# USB.net
KiCad netlist of a schematic drawn in Altium Designer
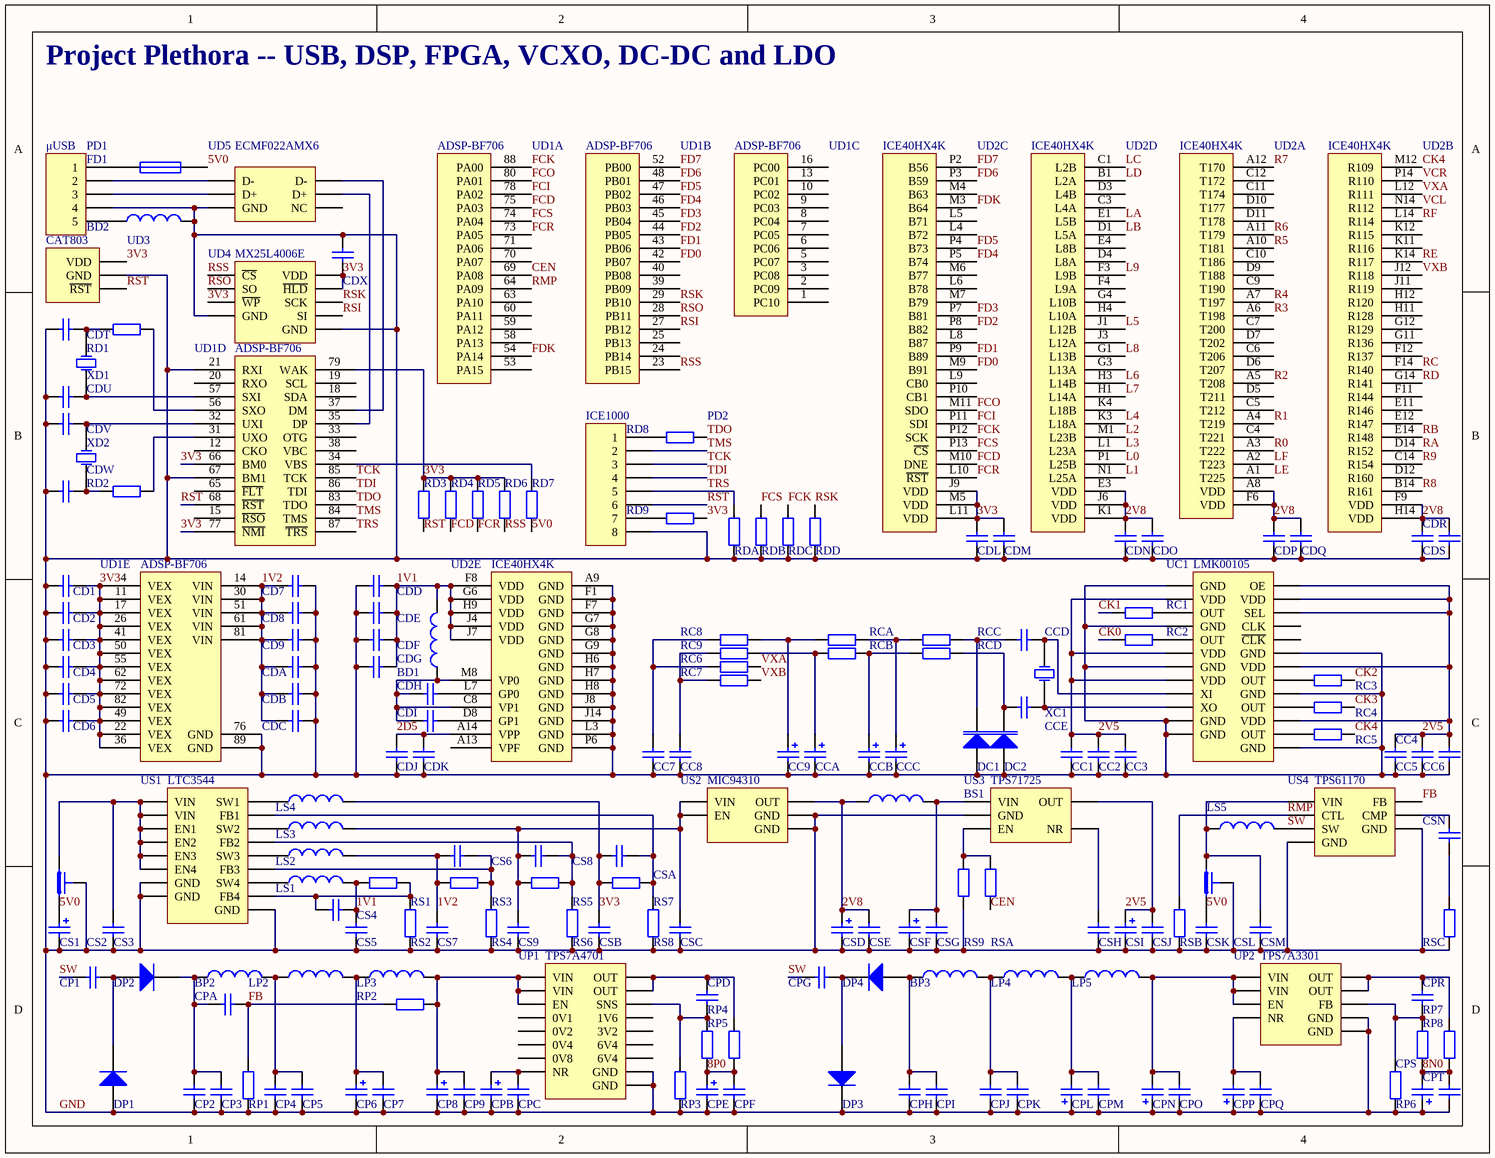
[diagram p0: USB.SchDoc]

(export (version "E")
  (design (tool "Eeschema 10.0.6"))
  (components
    (comp (ref "BD1")
      (value "Inductor")
      (footprint "0402")
      (fields (field (name "PUBLISHER") "Altium Limited"))
      (libsource (lib "Miscellaneous Devices") (part "Inductor"))
    )
    (comp (ref "BD2")
      (value "Inductor")
      (footprint "0402")
      (fields (field (name "PUBLISHER") "Altium Limited"))
      (libsource (lib "Miscellaneous Devices") (part "Inductor"))
    )
    (comp (ref "BP2")
      (value "Inductor")
      (footprint "0402")
      (fields (field (name "PUBLISHER") "Altium Limited"))
      (libsource (lib "Miscellaneous Devices") (part "Inductor"))
    )
    (comp (ref "BP3")
      (value "Inductor")
      (footprint "0402")
      (fields (field (name "PUBLISHER") "Altium Limited"))
      (libsource (lib "Miscellaneous Devices") (part "Inductor"))
    )
    (comp (ref "BS1")
      (value "Inductor")
      (footprint "0402")
      (fields (field (name "PUBLISHER") "Altium Limited"))
      (libsource (lib "Miscellaneous Devices") (part "Inductor"))
    )
    (comp (ref "CC1")
      (value "Cap")
      (footprint "0603")
      (description "Capacitor")
      (fields (field (name "PUBLISHER") "Altium Limited"))
      (libsource (lib "Miscellaneous Devices") (part "Cap"))
    )
    (comp (ref "CC2")
      (value "Cap")
      (footprint "0402")
      (description "Capacitor")
      (fields (field (name "PUBLISHER") "Altium Limited"))
      (libsource (lib "Miscellaneous Devices") (part "Cap"))
    )
    (comp (ref "CC3")
      (value "Cap")
      (footprint "0402")
      (description "Capacitor")
      (fields (field (name "PUBLISHER") "Altium Limited"))
      (libsource (lib "Miscellaneous Devices") (part "Cap"))
    )
    (comp (ref "CC4")
      (value "Cap")
      (footprint "0402")
      (description "Capacitor")
      (fields (field (name "PUBLISHER") "Altium Limited"))
      (libsource (lib "Miscellaneous Devices") (part "Cap"))
    )
    (comp (ref "CC5")
      (value "Cap")
      (footprint "0402")
      (description "Capacitor")
      (fields (field (name "PUBLISHER") "Altium Limited"))
      (libsource (lib "Miscellaneous Devices") (part "Cap"))
    )
    (comp (ref "CC6")
      (value "Cap")
      (footprint "0402")
      (description "Capacitor")
      (fields (field (name "PUBLISHER") "Altium Limited"))
      (libsource (lib "Miscellaneous Devices") (part "Cap"))
    )
    (comp (ref "CC7")
      (value "Cap")
      (footprint "0402")
      (description "Capacitor")
      (fields (field (name "PUBLISHER") "Altium Limited"))
      (libsource (lib "Miscellaneous Devices") (part "Cap"))
    )
    (comp (ref "CC8")
      (value "Cap")
      (footprint "0402")
      (description "Capacitor")
      (fields (field (name "PUBLISHER") "Altium Limited"))
      (libsource (lib "Miscellaneous Devices") (part "Cap"))
    )
    (comp (ref "CC9")
      (value "Cap Pol2")
      (footprint "0603")
      (description "Polarized Capacitor (Axial)")
      (fields (field (name "PUBLISHER") "Altium Limited"))
      (libsource (lib "Miscellaneous Devices") (part "Cap Pol2"))
    )
    (comp (ref "CCA")
      (value "Cap Pol2")
      (footprint "0603")
      (description "Polarized Capacitor (Axial)")
      (fields (field (name "PUBLISHER") "Altium Limited"))
      (libsource (lib "Miscellaneous Devices") (part "Cap Pol2"))
    )
    (comp (ref "CCB")
      (value "Cap Pol2")
      (footprint "0603")
      (description "Polarized Capacitor (Axial)")
      (fields (field (name "PUBLISHER") "Altium Limited"))
      (libsource (lib "Miscellaneous Devices") (part "Cap Pol2"))
    )
    (comp (ref "CCC")
      (value "Cap Pol2")
      (footprint "0603")
      (description "Polarized Capacitor (Axial)")
      (fields (field (name "PUBLISHER") "Altium Limited"))
      (libsource (lib "Miscellaneous Devices") (part "Cap Pol2"))
    )
    (comp (ref "CCD")
      (value "Cap")
      (footprint "0402")
      (description "Capacitor")
      (fields (field (name "PUBLISHER") "Altium Limited"))
      (libsource (lib "Miscellaneous Devices") (part "Cap"))
    )
    (comp (ref "CCE")
      (value "Cap")
      (footprint "0402")
      (description "Capacitor")
      (fields (field (name "PUBLISHER") "Altium Limited"))
      (libsource (lib "Miscellaneous Devices") (part "Cap"))
    )
    (comp (ref "CD1")
      (value "Cap")
      (footprint "0402")
      (description "Capacitor")
      (fields (field (name "PUBLISHER") "Altium Limited"))
      (libsource (lib "Miscellaneous Devices") (part "Cap"))
    )
    (comp (ref "CD2")
      (value "Cap")
      (footprint "0402")
      (description "Capacitor")
      (fields (field (name "PUBLISHER") "Altium Limited"))
      (libsource (lib "Miscellaneous Devices") (part "Cap"))
    )
    (comp (ref "CD3")
      (value "Cap")
      (footprint "0402")
      (description "Capacitor")
      (fields (field (name "PUBLISHER") "Altium Limited"))
      (libsource (lib "Miscellaneous Devices") (part "Cap"))
    )
    (comp (ref "CD4")
      (value "Cap")
      (footprint "0402")
      (description "Capacitor")
      (fields (field (name "PUBLISHER") "Altium Limited"))
      (libsource (lib "Miscellaneous Devices") (part "Cap"))
    )
    (comp (ref "CD5")
      (value "Cap")
      (footprint "0402")
      (description "Capacitor")
      (fields (field (name "PUBLISHER") "Altium Limited"))
      (libsource (lib "Miscellaneous Devices") (part "Cap"))
    )
    (comp (ref "CD6")
      (value "Cap")
      (footprint "0402")
      (description "Capacitor")
      (fields (field (name "PUBLISHER") "Altium Limited"))
      (libsource (lib "Miscellaneous Devices") (part "Cap"))
    )
    (comp (ref "CD7")
      (value "Cap")
      (footprint "0402")
      (description "Capacitor")
      (fields (field (name "PUBLISHER") "Altium Limited"))
      (libsource (lib "Miscellaneous Devices") (part "Cap"))
    )
    (comp (ref "CD8")
      (value "Cap")
      (footprint "0402")
      (description "Capacitor")
      (fields (field (name "PUBLISHER") "Altium Limited"))
      (libsource (lib "Miscellaneous Devices") (part "Cap"))
    )
    (comp (ref "CD9")
      (value "Cap")
      (footprint "0402")
      (description "Capacitor")
      (fields (field (name "PUBLISHER") "Altium Limited"))
      (libsource (lib "Miscellaneous Devices") (part "Cap"))
    )
    (comp (ref "CDA")
      (value "Cap")
      (footprint "0402")
      (description "Capacitor")
      (fields (field (name "PUBLISHER") "Altium Limited"))
      (libsource (lib "Miscellaneous Devices") (part "Cap"))
    )
    (comp (ref "CDB")
      (value "Cap")
      (footprint "0402")
      (description "Capacitor")
      (fields (field (name "PUBLISHER") "Altium Limited"))
      (libsource (lib "Miscellaneous Devices") (part "Cap"))
    )
    (comp (ref "CDC")
      (value "Cap")
      (footprint "0402")
      (description "Capacitor")
      (fields (field (name "PUBLISHER") "Altium Limited"))
      (libsource (lib "Miscellaneous Devices") (part "Cap"))
    )
    (comp (ref "CDD")
      (value "Cap")
      (footprint "0402")
      (description "Capacitor")
      (fields (field (name "PUBLISHER") "Altium Limited"))
      (libsource (lib "Miscellaneous Devices") (part "Cap"))
    )
    (comp (ref "CDE")
      (value "Cap")
      (footprint "0402")
      (description "Capacitor")
      (fields (field (name "PUBLISHER") "Altium Limited"))
      (libsource (lib "Miscellaneous Devices") (part "Cap"))
    )
    (comp (ref "CDF")
      (value "Cap")
      (footprint "0402")
      (description "Capacitor")
      (fields (field (name "PUBLISHER") "Altium Limited"))
      (libsource (lib "Miscellaneous Devices") (part "Cap"))
    )
    (comp (ref "CDG")
      (value "Cap")
      (footprint "0402")
      (description "Capacitor")
      (fields (field (name "PUBLISHER") "Altium Limited"))
      (libsource (lib "Miscellaneous Devices") (part "Cap"))
    )
    (comp (ref "CDH")
      (value "Cap")
      (footprint "0402")
      (description "Capacitor")
      (fields (field (name "PUBLISHER") "Altium Limited"))
      (libsource (lib "Miscellaneous Devices") (part "Cap"))
    )
    (comp (ref "CDI")
      (value "Cap")
      (footprint "0402")
      (description "Capacitor")
      (fields (field (name "PUBLISHER") "Altium Limited"))
      (libsource (lib "Miscellaneous Devices") (part "Cap"))
    )
    (comp (ref "CDJ")
      (value "Cap")
      (footprint "0402")
      (description "Capacitor")
      (fields (field (name "PUBLISHER") "Altium Limited"))
      (libsource (lib "Miscellaneous Devices") (part "Cap"))
    )
    (comp (ref "CDK")
      (value "Cap")
      (footprint "0402")
      (description "Capacitor")
      (fields (field (name "PUBLISHER") "Altium Limited"))
      (libsource (lib "Miscellaneous Devices") (part "Cap"))
    )
    (comp (ref "CDL")
      (value "Cap")
      (footprint "0402")
      (description "Capacitor")
      (fields (field (name "PUBLISHER") "Altium Limited"))
      (libsource (lib "Miscellaneous Devices") (part "Cap"))
    )
    (comp (ref "CDM")
      (value "Cap")
      (footprint "0402")
      (description "Capacitor")
      (fields (field (name "PUBLISHER") "Altium Limited"))
      (libsource (lib "Miscellaneous Devices") (part "Cap"))
    )
    (comp (ref "CDN")
      (value "Cap")
      (footprint "0402")
      (description "Capacitor")
      (fields (field (name "PUBLISHER") "Altium Limited"))
      (libsource (lib "Miscellaneous Devices") (part "Cap"))
    )
    (comp (ref "CDO")
      (value "Cap")
      (footprint "0402")
      (description "Capacitor")
      (fields (field (name "PUBLISHER") "Altium Limited"))
      (libsource (lib "Miscellaneous Devices") (part "Cap"))
    )
    (comp (ref "CDP")
      (value "Cap")
      (footprint "0402")
      (description "Capacitor")
      (fields (field (name "PUBLISHER") "Altium Limited"))
      (libsource (lib "Miscellaneous Devices") (part "Cap"))
    )
    (comp (ref "CDQ")
      (value "Cap")
      (footprint "0402")
      (description "Capacitor")
      (fields (field (name "PUBLISHER") "Altium Limited"))
      (libsource (lib "Miscellaneous Devices") (part "Cap"))
    )
    (comp (ref "CDR")
      (value "Cap")
      (footprint "0402")
      (description "Capacitor")
      (fields (field (name "PUBLISHER") "Altium Limited"))
      (libsource (lib "Miscellaneous Devices") (part "Cap"))
    )
    (comp (ref "CDS")
      (value "Cap")
      (footprint "0402")
      (description "Capacitor")
      (fields (field (name "PUBLISHER") "Altium Limited"))
      (libsource (lib "Miscellaneous Devices") (part "Cap"))
    )
    (comp (ref "CDT")
      (value "Cap")
      (footprint "0402")
      (description "Capacitor")
      (fields (field (name "PUBLISHER") "Altium Limited"))
      (libsource (lib "Miscellaneous Devices") (part "Cap"))
    )
    (comp (ref "CDU")
      (value "Cap")
      (footprint "0402")
      (description "Capacitor")
      (fields (field (name "PUBLISHER") "Altium Limited"))
      (libsource (lib "Miscellaneous Devices") (part "Cap"))
    )
    (comp (ref "CDV")
      (value "Cap")
      (footprint "0402")
      (description "Capacitor")
      (fields (field (name "PUBLISHER") "Altium Limited"))
      (libsource (lib "Miscellaneous Devices") (part "Cap"))
    )
    (comp (ref "CDW")
      (value "Cap")
      (footprint "0402")
      (description "Capacitor")
      (fields (field (name "PUBLISHER") "Altium Limited"))
      (libsource (lib "Miscellaneous Devices") (part "Cap"))
    )
    (comp (ref "CDX")
      (value "Cap")
      (footprint "0402")
      (description "Capacitor")
      (fields (field (name "PUBLISHER") "Altium Limited"))
      (libsource (lib "Miscellaneous Devices") (part "Cap"))
    )
    (comp (ref "CP1")
      (value "Cap")
      (footprint "0402")
      (description "Capacitor")
      (fields (field (name "PUBLISHER") "Altium Limited"))
      (libsource (lib "Miscellaneous Devices") (part "Cap"))
    )
    (comp (ref "CP2")
      (value "Cap")
      (footprint "0805")
      (description "Capacitor")
      (fields (field (name "PUBLISHER") "Altium Limited"))
      (libsource (lib "Miscellaneous Devices") (part "Cap"))
    )
    (comp (ref "CP3")
      (value "Cap")
      (footprint "0805")
      (description "Capacitor")
      (fields (field (name "PUBLISHER") "Altium Limited"))
      (libsource (lib "Miscellaneous Devices") (part "Cap"))
    )
    (comp (ref "CP4")
      (value "Cap")
      (footprint "0805")
      (description "Capacitor")
      (fields (field (name "PUBLISHER") "Altium Limited"))
      (libsource (lib "Miscellaneous Devices") (part "Cap"))
    )
    (comp (ref "CP5")
      (value "Cap")
      (footprint "0805")
      (description "Capacitor")
      (fields (field (name "PUBLISHER") "Altium Limited"))
      (libsource (lib "Miscellaneous Devices") (part "Cap"))
    )
    (comp (ref "CP6")
      (value "Cap Pol2")
      (footprint "6032")
      (description "Polarized Capacitor (Axial)")
      (fields (field (name "PUBLISHER") "Altium Limited"))
      (libsource (lib "Miscellaneous Devices") (part "Cap Pol2"))
    )
    (comp (ref "CP7")
      (value "Cap")
      (footprint "0805")
      (description "Capacitor")
      (fields (field (name "PUBLISHER") "Altium Limited"))
      (libsource (lib "Miscellaneous Devices") (part "Cap"))
    )
    (comp (ref "CP8")
      (value "Cap Pol2")
      (footprint "6032")
      (description "Polarized Capacitor (Axial)")
      (fields (field (name "PUBLISHER") "Altium Limited"))
      (libsource (lib "Miscellaneous Devices") (part "Cap Pol2"))
    )
    (comp (ref "CP9")
      (value "Cap")
      (footprint "0805")
      (description "Capacitor")
      (fields (field (name "PUBLISHER") "Altium Limited"))
      (libsource (lib "Miscellaneous Devices") (part "Cap"))
    )
    (comp (ref "CPA")
      (value "Cap")
      (footprint "0402")
      (description "Capacitor")
      (fields (field (name "PUBLISHER") "Altium Limited"))
      (libsource (lib "Miscellaneous Devices") (part "Cap"))
    )
    (comp (ref "CPB")
      (value "Cap Pol2")
      (footprint "0603")
      (description "Polarized Capacitor (Axial)")
      (fields (field (name "PUBLISHER") "Altium Limited"))
      (libsource (lib "Miscellaneous Devices") (part "Cap Pol2"))
    )
    (comp (ref "CPC")
      (value "Cap")
      (footprint "0603")
      (description "Capacitor")
      (fields (field (name "PUBLISHER") "Altium Limited"))
      (libsource (lib "Miscellaneous Devices") (part "Cap"))
    )
    (comp (ref "CPD")
      (value "Cap")
      (footprint "0402")
      (description "Capacitor")
      (fields (field (name "PUBLISHER") "Altium Limited"))
      (libsource (lib "Miscellaneous Devices") (part "Cap"))
    )
    (comp (ref "CPE")
      (value "Cap Pol2")
      (footprint "6032")
      (description "Polarized Capacitor (Axial)")
      (fields (field (name "PUBLISHER") "Altium Limited"))
      (libsource (lib "Miscellaneous Devices") (part "Cap Pol2"))
    )
    (comp (ref "CPF")
      (value "Cap")
      (footprint "0805")
      (description "Capacitor")
      (fields (field (name "PUBLISHER") "Altium Limited"))
      (libsource (lib "Miscellaneous Devices") (part "Cap"))
    )
    (comp (ref "CPG")
      (value "Cap")
      (footprint "0402")
      (description "Capacitor")
      (fields (field (name "PUBLISHER") "Altium Limited"))
      (libsource (lib "Miscellaneous Devices") (part "Cap"))
    )
    (comp (ref "CPH")
      (value "Cap")
      (footprint "0805")
      (description "Capacitor")
      (fields (field (name "PUBLISHER") "Altium Limited"))
      (libsource (lib "Miscellaneous Devices") (part "Cap"))
    )
    (comp (ref "CPI")
      (value "Cap")
      (footprint "0805")
      (description "Capacitor")
      (fields (field (name "PUBLISHER") "Altium Limited"))
      (libsource (lib "Miscellaneous Devices") (part "Cap"))
    )
    (comp (ref "CPJ")
      (value "Cap")
      (footprint "0805")
      (description "Capacitor")
      (fields (field (name "PUBLISHER") "Altium Limited"))
      (libsource (lib "Miscellaneous Devices") (part "Cap"))
    )
    (comp (ref "CPK")
      (value "Cap")
      (footprint "0805")
      (description "Capacitor")
      (fields (field (name "PUBLISHER") "Altium Limited"))
      (libsource (lib "Miscellaneous Devices") (part "Cap"))
    )
    (comp (ref "CPL")
      (value "Cap Pol2")
      (footprint "6032")
      (description "Polarized Capacitor (Axial)")
      (fields (field (name "PUBLISHER") "Altium Limited"))
      (libsource (lib "Miscellaneous Devices") (part "Cap Pol2"))
    )
    (comp (ref "CPM")
      (value "Cap")
      (footprint "0805")
      (description "Capacitor")
      (fields (field (name "PUBLISHER") "Altium Limited"))
      (libsource (lib "Miscellaneous Devices") (part "Cap"))
    )
    (comp (ref "CPN")
      (value "Cap Pol2")
      (footprint "6032")
      (description "Polarized Capacitor (Axial)")
      (fields (field (name "PUBLISHER") "Altium Limited"))
      (libsource (lib "Miscellaneous Devices") (part "Cap Pol2"))
    )
    (comp (ref "CPO")
      (value "Cap")
      (footprint "0805")
      (description "Capacitor")
      (fields (field (name "PUBLISHER") "Altium Limited"))
      (libsource (lib "Miscellaneous Devices") (part "Cap"))
    )
    (comp (ref "CPP")
      (value "Cap Pol2")
      (footprint "0603")
      (description "Polarized Capacitor (Axial)")
      (fields (field (name "PUBLISHER") "Altium Limited"))
      (libsource (lib "Miscellaneous Devices") (part "Cap Pol2"))
    )
    (comp (ref "CPQ")
      (value "Cap")
      (footprint "0603")
      (description "Capacitor")
      (fields (field (name "PUBLISHER") "Altium Limited"))
      (libsource (lib "Miscellaneous Devices") (part "Cap"))
    )
    (comp (ref "CPR")
      (value "Cap")
      (footprint "0402")
      (description "Capacitor")
      (fields (field (name "PUBLISHER") "Altium Limited"))
      (libsource (lib "Miscellaneous Devices") (part "Cap"))
    )
    (comp (ref "CPS")
      (value "Cap Pol2")
      (footprint "6032")
      (description "Polarized Capacitor (Axial)")
      (fields (field (name "PUBLISHER") "Altium Limited"))
      (libsource (lib "Miscellaneous Devices") (part "Cap Pol2"))
    )
    (comp (ref "CPT")
      (value "Cap")
      (footprint "0805")
      (description "Capacitor")
      (fields (field (name "PUBLISHER") "Altium Limited"))
      (libsource (lib "Miscellaneous Devices") (part "Cap"))
    )
    (comp (ref "CS1")
      (value "Cap Pol2")
      (footprint "0603")
      (description "Polarized Capacitor (Axial)")
      (fields (field (name "PUBLISHER") "Altium Limited"))
      (libsource (lib "Miscellaneous Devices") (part "Cap Pol2"))
    )
    (comp (ref "CS2")
      (value "Cap Feed")
      (footprint "0603F")
      (description "Feed-Through Capacitor")
      (fields (field (name "PUBLISHER") "Altium Limited"))
      (libsource (lib "Miscellaneous Devices") (part "Cap Feed"))
    )
    (comp (ref "CS3")
      (value "Cap")
      (footprint "0402")
      (description "Capacitor")
      (fields (field (name "PUBLISHER") "Altium Limited"))
      (libsource (lib "Miscellaneous Devices") (part "Cap"))
    )
    (comp (ref "CS4")
      (value "Cap")
      (footprint "0402")
      (description "Capacitor")
      (fields (field (name "PUBLISHER") "Altium Limited"))
      (libsource (lib "Miscellaneous Devices") (part "Cap"))
    )
    (comp (ref "CS5")
      (value "Cap")
      (footprint "0603")
      (description "Capacitor")
      (fields (field (name "PUBLISHER") "Altium Limited"))
      (libsource (lib "Miscellaneous Devices") (part "Cap"))
    )
    (comp (ref "CS6")
      (value "Cap")
      (footprint "0402")
      (description "Capacitor")
      (fields (field (name "PUBLISHER") "Altium Limited"))
      (libsource (lib "Miscellaneous Devices") (part "Cap"))
    )
    (comp (ref "CS7")
      (value "Cap")
      (footprint "0603")
      (description "Capacitor")
      (fields (field (name "PUBLISHER") "Altium Limited"))
      (libsource (lib "Miscellaneous Devices") (part "Cap"))
    )
    (comp (ref "CS8")
      (value "Cap")
      (footprint "0402")
      (description "Capacitor")
      (fields (field (name "PUBLISHER") "Altium Limited"))
      (libsource (lib "Miscellaneous Devices") (part "Cap"))
    )
    (comp (ref "CS9")
      (value "Cap")
      (footprint "0603")
      (description "Capacitor")
      (fields (field (name "PUBLISHER") "Altium Limited"))
      (libsource (lib "Miscellaneous Devices") (part "Cap"))
    )
    (comp (ref "CSA")
      (value "Cap")
      (footprint "0402")
      (description "Capacitor")
      (fields (field (name "PUBLISHER") "Altium Limited"))
      (libsource (lib "Miscellaneous Devices") (part "Cap"))
    )
    (comp (ref "CSB")
      (value "Cap")
      (footprint "0603")
      (description "Capacitor")
      (fields (field (name "PUBLISHER") "Altium Limited"))
      (libsource (lib "Miscellaneous Devices") (part "Cap"))
    )
    (comp (ref "CSC")
      (value "Cap")
      (footprint "0402")
      (description "Capacitor")
      (fields (field (name "PUBLISHER") "Altium Limited"))
      (libsource (lib "Miscellaneous Devices") (part "Cap"))
    )
    (comp (ref "CSD")
      (value "Cap Pol2")
      (footprint "0603")
      (description "Polarized Capacitor (Axial)")
      (fields (field (name "PUBLISHER") "Altium Limited"))
      (libsource (lib "Miscellaneous Devices") (part "Cap Pol2"))
    )
    (comp (ref "CSE")
      (value "Cap")
      (footprint "0603")
      (description "Capacitor")
      (fields (field (name "PUBLISHER") "Altium Limited"))
      (libsource (lib "Miscellaneous Devices") (part "Cap"))
    )
    (comp (ref "CSF")
      (value "Cap Pol2")
      (footprint "0603")
      (description "Polarized Capacitor (Axial)")
      (fields (field (name "PUBLISHER") "Altium Limited"))
      (libsource (lib "Miscellaneous Devices") (part "Cap Pol2"))
    )
    (comp (ref "CSG")
      (value "Cap")
      (footprint "0603")
      (description "Capacitor")
      (fields (field (name "PUBLISHER") "Altium Limited"))
      (libsource (lib "Miscellaneous Devices") (part "Cap"))
    )
    (comp (ref "CSH")
      (value "Cap")
      (footprint "0603")
      (description "Capacitor")
      (fields (field (name "PUBLISHER") "Altium Limited"))
      (libsource (lib "Miscellaneous Devices") (part "Cap"))
    )
    (comp (ref "CSI")
      (value "Cap Pol2")
      (footprint "0603")
      (description "Polarized Capacitor (Axial)")
      (fields (field (name "PUBLISHER") "Altium Limited"))
      (libsource (lib "Miscellaneous Devices") (part "Cap Pol2"))
    )
    (comp (ref "CSJ")
      (value "Cap")
      (footprint "0603")
      (description "Capacitor")
      (fields (field (name "PUBLISHER") "Altium Limited"))
      (libsource (lib "Miscellaneous Devices") (part "Cap"))
    )
    (comp (ref "CSK")
      (value "Cap")
      (footprint "0402")
      (description "Capacitor")
      (fields (field (name "PUBLISHER") "Altium Limited"))
      (libsource (lib "Miscellaneous Devices") (part "Cap"))
    )
    (comp (ref "CSL")
      (value "Cap Feed")
      (footprint "0603F")
      (description "Feed-Through Capacitor")
      (fields (field (name "PUBLISHER") "Altium Limited"))
      (libsource (lib "Miscellaneous Devices") (part "Cap Feed"))
    )
    (comp (ref "CSM")
      (value "Cap")
      (footprint "0402")
      (description "Capacitor")
      (fields (field (name "PUBLISHER") "Altium Limited"))
      (libsource (lib "Miscellaneous Devices") (part "Cap"))
    )
    (comp (ref "CSN")
      (value "Cap")
      (footprint "0402")
      (description "Capacitor")
      (fields (field (name "PUBLISHER") "Altium Limited"))
      (libsource (lib "Miscellaneous Devices") (part "Cap"))
    )
    (comp (ref "DC1")
      (value "D Varactor")
      (footprint "SOD523")
      (description "Variable Capacitance Diode")
      (fields (field (name "PUBLISHER") "Altium Limited"))
      (libsource (lib "Miscellaneous Devices") (part "D Varactor"))
    )
    (comp (ref "DC2")
      (value "D Varactor")
      (footprint "SOD523")
      (description "Variable Capacitance Diode")
      (fields (field (name "PUBLISHER") "Altium Limited"))
      (libsource (lib "Miscellaneous Devices") (part "D Varactor"))
    )
    (comp (ref "DP1")
      (value "Diode")
      (footprint "SOD882")
      (description "Default Diode")
      (fields (field (name "PUBLISHER") "Altium Limited"))
      (libsource (lib "Miscellaneous Devices") (part "Diode"))
    )
    (comp (ref "DP2")
      (value "Diode")
      (footprint "SOD882")
      (description "Default Diode")
      (fields (field (name "PUBLISHER") "Altium Limited"))
      (libsource (lib "Miscellaneous Devices") (part "Diode"))
    )
    (comp (ref "DP3")
      (value "Diode")
      (footprint "SOD882")
      (description "Default Diode")
      (fields (field (name "PUBLISHER") "Altium Limited"))
      (libsource (lib "Miscellaneous Devices") (part "Diode"))
    )
    (comp (ref "DP4")
      (value "Diode")
      (footprint "SOD882")
      (description "Default Diode")
      (fields (field (name "PUBLISHER") "Altium Limited"))
      (libsource (lib "Miscellaneous Devices") (part "Diode"))
    )
    (comp (ref "FD1")
      (value "Fuse 1")
      (footprint "0402")
      (description "Fuse")
      (fields (field (name "PUBLISHER") "Altium Limited"))
      (libsource (lib "Miscellaneous Devices") (part "Fuse 1"))
    )
    (comp (ref "LP2")
      (value "Inductor")
      (footprint "1210")
      (fields (field (name "PUBLISHER") "Altium Limited"))
      (libsource (lib "Miscellaneous Devices") (part "Inductor"))
    )
    (comp (ref "LP3")
      (value "Inductor")
      (footprint "1210")
      (fields (field (name "PUBLISHER") "Altium Limited"))
      (libsource (lib "Miscellaneous Devices") (part "Inductor"))
    )
    (comp (ref "LP4")
      (value "Inductor")
      (footprint "1210")
      (fields (field (name "PUBLISHER") "Altium Limited"))
      (libsource (lib "Miscellaneous Devices") (part "Inductor"))
    )
    (comp (ref "LP5")
      (value "Inductor")
      (footprint "1210")
      (fields (field (name "PUBLISHER") "Altium Limited"))
      (libsource (lib "Miscellaneous Devices") (part "Inductor"))
    )
    (comp (ref "LS1")
      (value "Inductor")
      (footprint "0805")
      (fields (field (name "PUBLISHER") "Altium Limited"))
      (libsource (lib "Miscellaneous Devices") (part "Inductor"))
    )
    (comp (ref "LS2")
      (value "Inductor")
      (footprint "0805")
      (fields (field (name "PUBLISHER") "Altium Limited"))
      (libsource (lib "Miscellaneous Devices") (part "Inductor"))
    )
    (comp (ref "LS3")
      (value "Inductor")
      (footprint "0805")
      (fields (field (name "PUBLISHER") "Altium Limited"))
      (libsource (lib "Miscellaneous Devices") (part "Inductor"))
    )
    (comp (ref "LS4")
      (value "Inductor")
      (footprint "0805")
      (fields (field (name "PUBLISHER") "Altium Limited"))
      (libsource (lib "Miscellaneous Devices") (part "Inductor"))
    )
    (comp (ref "LS5")
      (value "Inductor")
      (footprint "SRP2010")
      (fields (field (name "PUBLISHER") "Altium Limited"))
      (libsource (lib "Miscellaneous Devices") (part "Inductor"))
    )
    (comp (ref "PD1")
      (value "μUSB")
      (footprint "HDR1X5")
      (description "Header, 5-Pin")
      (fields (field (name "PUBLISHER") "Altium Limited"))
      (libsource (lib "Miscellaneous Connectors") (part "Header 5"))
    )
    (comp (ref "PD2")
      (value "ICE1000")
      (footprint "SOLO9188")
      (description "Header, 8-Pin")
      (fields (field (name "PUBLISHER") "Altium Limited"))
      (libsource (lib "Miscellaneous Connectors") (part "Header 8"))
    )
    (comp (ref "RC1")
      (value "Res2")
      (footprint "0402")
      (description "Resistor")
      (fields (field (name "PUBLISHER") "Altium Limited"))
      (libsource (lib "Miscellaneous Devices") (part "Res2"))
    )
    (comp (ref "RC2")
      (value "Res2")
      (footprint "0402")
      (description "Resistor")
      (fields (field (name "PUBLISHER") "Altium Limited"))
      (libsource (lib "Miscellaneous Devices") (part "Res2"))
    )
    (comp (ref "RC3")
      (value "Res2")
      (footprint "0402")
      (description "Resistor")
      (fields (field (name "PUBLISHER") "Altium Limited"))
      (libsource (lib "Miscellaneous Devices") (part "Res2"))
    )
    (comp (ref "RC4")
      (value "Res2")
      (footprint "0402")
      (description "Resistor")
      (fields (field (name "PUBLISHER") "Altium Limited"))
      (libsource (lib "Miscellaneous Devices") (part "Res2"))
    )
    (comp (ref "RC5")
      (value "Res2")
      (footprint "0402")
      (description "Resistor")
      (fields (field (name "PUBLISHER") "Altium Limited"))
      (libsource (lib "Miscellaneous Devices") (part "Res2"))
    )
    (comp (ref "RC6")
      (value "Res2")
      (footprint "0402")
      (description "Resistor")
      (fields (field (name "PUBLISHER") "Altium Limited"))
      (libsource (lib "Miscellaneous Devices") (part "Res2"))
    )
    (comp (ref "RC7")
      (value "Res2")
      (footprint "0402")
      (description "Resistor")
      (fields (field (name "PUBLISHER") "Altium Limited"))
      (libsource (lib "Miscellaneous Devices") (part "Res2"))
    )
    (comp (ref "RC8")
      (value "Res2")
      (footprint "0402")
      (description "Resistor")
      (fields (field (name "PUBLISHER") "Altium Limited"))
      (libsource (lib "Miscellaneous Devices") (part "Res2"))
    )
    (comp (ref "RC9")
      (value "Res2")
      (footprint "0402")
      (description "Resistor")
      (fields (field (name "PUBLISHER") "Altium Limited"))
      (libsource (lib "Miscellaneous Devices") (part "Res2"))
    )
    (comp (ref "RCA")
      (value "Res2")
      (footprint "0402")
      (description "Resistor")
      (fields (field (name "PUBLISHER") "Altium Limited"))
      (libsource (lib "Miscellaneous Devices") (part "Res2"))
    )
    (comp (ref "RCB")
      (value "Res2")
      (footprint "0402")
      (description "Resistor")
      (fields (field (name "PUBLISHER") "Altium Limited"))
      (libsource (lib "Miscellaneous Devices") (part "Res2"))
    )
    (comp (ref "RCC")
      (value "Res2")
      (footprint "0402")
      (description "Resistor")
      (fields (field (name "PUBLISHER") "Altium Limited"))
      (libsource (lib "Miscellaneous Devices") (part "Res2"))
    )
    (comp (ref "RCD")
      (value "Res2")
      (footprint "0402")
      (description "Resistor")
      (fields (field (name "PUBLISHER") "Altium Limited"))
      (libsource (lib "Miscellaneous Devices") (part "Res2"))
    )
    (comp (ref "RD1")
      (value "Res2")
      (footprint "0402")
      (description "Resistor")
      (fields (field (name "PUBLISHER") "Altium Limited"))
      (libsource (lib "Miscellaneous Devices") (part "Res2"))
    )
    (comp (ref "RD2")
      (value "Res2")
      (footprint "0402")
      (description "Resistor")
      (fields (field (name "PUBLISHER") "Altium Limited"))
      (libsource (lib "Miscellaneous Devices") (part "Res2"))
    )
    (comp (ref "RD3")
      (value "Res2")
      (footprint "0402")
      (description "Resistor")
      (fields (field (name "PUBLISHER") "Altium Limited"))
      (libsource (lib "") (part "Res2_1"))
    )
    (comp (ref "RD4")
      (value "Res2")
      (footprint "0402")
      (description "Resistor")
      (fields (field (name "PUBLISHER") "Altium Limited"))
      (libsource (lib "") (part "Res2_1"))
    )
    (comp (ref "RD5")
      (value "Res2")
      (footprint "0402")
      (description "Resistor")
      (fields (field (name "PUBLISHER") "Altium Limited"))
      (libsource (lib "") (part "Res2_1"))
    )
    (comp (ref "RD6")
      (value "Res2")
      (footprint "0402")
      (description "Resistor")
      (fields (field (name "PUBLISHER") "Altium Limited"))
      (libsource (lib "") (part "Res2_1"))
    )
    (comp (ref "RD7")
      (value "Res2")
      (footprint "0402")
      (description "Resistor")
      (fields (field (name "PUBLISHER") "Altium Limited"))
      (libsource (lib "") (part "Res2_1"))
    )
    (comp (ref "RD8")
      (value "Res2")
      (footprint "0402")
      (description "Resistor")
      (fields (field (name "PUBLISHER") "Altium Limited"))
      (libsource (lib "Miscellaneous Devices") (part "Res2"))
    )
    (comp (ref "RD9")
      (value "Res2")
      (footprint "0402")
      (description "Resistor")
      (fields (field (name "PUBLISHER") "Altium Limited"))
      (libsource (lib "Miscellaneous Devices") (part "Res2"))
    )
    (comp (ref "RDA")
      (value "Res2")
      (footprint "0402")
      (description "Resistor")
      (fields (field (name "PUBLISHER") "Altium Limited"))
      (libsource (lib "") (part "Res2_1"))
    )
    (comp (ref "RDB")
      (value "Res2")
      (footprint "0402")
      (description "Resistor")
      (fields (field (name "PUBLISHER") "Altium Limited"))
      (libsource (lib "") (part "Res2_1"))
    )
    (comp (ref "RDC")
      (value "Res2")
      (footprint "0402")
      (description "Resistor")
      (fields (field (name "PUBLISHER") "Altium Limited"))
      (libsource (lib "") (part "Res2_1"))
    )
    (comp (ref "RDD")
      (value "Res2")
      (footprint "0402")
      (description "Resistor")
      (fields (field (name "PUBLISHER") "Altium Limited"))
      (libsource (lib "") (part "Res2_1"))
    )
    (comp (ref "RP1")
      (value "Res2")
      (footprint "0402")
      (description "Resistor")
      (fields (field (name "PUBLISHER") "Altium Limited"))
      (libsource (lib "") (part "Res2_1"))
    )
    (comp (ref "RP2")
      (value "Res2")
      (footprint "0402")
      (description "Resistor")
      (fields (field (name "PUBLISHER") "Altium Limited"))
      (libsource (lib "Miscellaneous Devices") (part "Res2"))
    )
    (comp (ref "RP3")
      (value "Res2")
      (footprint "0402")
      (description "Resistor")
      (fields (field (name "PUBLISHER") "Altium Limited"))
      (libsource (lib "") (part "Res2_2"))
    )
    (comp (ref "RP4")
      (value "Res2")
      (footprint "0402")
      (description "Resistor")
      (fields (field (name "PUBLISHER") "Altium Limited"))
      (libsource (lib "") (part "Res2_1"))
    )
    (comp (ref "RP5")
      (value "Res2")
      (footprint "0402")
      (description "Resistor")
      (fields (field (name "PUBLISHER") "Altium Limited"))
      (libsource (lib "") (part "Res2_1"))
    )
    (comp (ref "RP6")
      (value "Res2")
      (footprint "0402")
      (description "Resistor")
      (fields (field (name "PUBLISHER") "Altium Limited"))
      (libsource (lib "") (part "Res2_1"))
    )
    (comp (ref "RP7")
      (value "Res2")
      (footprint "0402")
      (description "Resistor")
      (fields (field (name "PUBLISHER") "Altium Limited"))
      (libsource (lib "") (part "Res2_1"))
    )
    (comp (ref "RP8")
      (value "Res2")
      (footprint "0402")
      (description "Resistor")
      (fields (field (name "PUBLISHER") "Altium Limited"))
      (libsource (lib "") (part "Res2_1"))
    )
    (comp (ref "RS1")
      (value "Res2")
      (footprint "0402")
      (description "Resistor")
      (fields (field (name "PUBLISHER") "Altium Limited"))
      (libsource (lib "Miscellaneous Devices") (part "Res2"))
    )
    (comp (ref "RS2")
      (value "Res2")
      (footprint "0402")
      (description "Resistor")
      (fields (field (name "PUBLISHER") "Altium Limited"))
      (libsource (lib "") (part "Res2_1"))
    )
    (comp (ref "RS3")
      (value "Res2")
      (footprint "0402")
      (description "Resistor")
      (fields (field (name "PUBLISHER") "Altium Limited"))
      (libsource (lib "Miscellaneous Devices") (part "Res2"))
    )
    (comp (ref "RS4")
      (value "Res2")
      (footprint "0402")
      (description "Resistor")
      (fields (field (name "PUBLISHER") "Altium Limited"))
      (libsource (lib "") (part "Res2_1"))
    )
    (comp (ref "RS5")
      (value "Res2")
      (footprint "0402")
      (description "Resistor")
      (fields (field (name "PUBLISHER") "Altium Limited"))
      (libsource (lib "Miscellaneous Devices") (part "Res2"))
    )
    (comp (ref "RS6")
      (value "Res2")
      (footprint "0402")
      (description "Resistor")
      (fields (field (name "PUBLISHER") "Altium Limited"))
      (libsource (lib "") (part "Res2_1"))
    )
    (comp (ref "RS7")
      (value "Res2")
      (footprint "0402")
      (description "Resistor")
      (fields (field (name "PUBLISHER") "Altium Limited"))
      (libsource (lib "Miscellaneous Devices") (part "Res2"))
    )
    (comp (ref "RS8")
      (value "Res2")
      (footprint "0402")
      (description "Resistor")
      (fields (field (name "PUBLISHER") "Altium Limited"))
      (libsource (lib "") (part "Res2_1"))
    )
    (comp (ref "RS9")
      (value "Res2")
      (footprint "0402")
      (description "Resistor")
      (fields (field (name "PUBLISHER") "Altium Limited"))
      (libsource (lib "") (part "Res2_1"))
    )
    (comp (ref "RSA")
      (value "Res2")
      (footprint "0402")
      (description "Resistor")
      (fields (field (name "PUBLISHER") "Altium Limited"))
      (libsource (lib "") (part "Res2_1"))
    )
    (comp (ref "RSB")
      (value "Res2")
      (footprint "0402")
      (description "Resistor")
      (fields (field (name "PUBLISHER") "Altium Limited"))
      (libsource (lib "") (part "Res2_1"))
    )
    (comp (ref "RSC")
      (value "Res2")
      (footprint "0402")
      (description "Resistor")
      (fields (field (name "PUBLISHER") "Altium Limited"))
      (libsource (lib "") (part "Res2_1"))
    )
    (comp (ref "UC1") (value "LMK00105") (footprint "QFN24") (libsource (lib "UDAC") (part "LMK00105")))
    (comp (ref "UD1") (value "ADSP-BF706") (footprint "QFN88") (libsource (lib "UDAC") (part "ADSP-BF706")))
    (comp (ref "UD2")
      (value "ICE40HX4K")
      (footprint "BGA132")
      (fields
        (field (name "MANUFACTURER") "Lattice Semiconductor")
        (field (name "PARTNUMBER") "ICE40HX4K-CB132")
      )
      (libsource (lib "UDAC") (part "ICE40HX4K"))
    )
    (comp (ref "UD3") (value "CAT803") (footprint "SC70") (libsource (lib "UDAC") (part "CAT803")))
    (comp (ref "UD4") (value "MX25L4006E") (footprint "UDFN8") (libsource (lib "UDAC") (part "MX25L4006E")))
    (comp (ref "UD5") (value "ECMF022AMX6") (footprint "UDFN6") (libsource (lib "UDAC") (part "ECMF022AMX6")))
    (comp (ref "UP1") (value "TPS7A4701") (footprint "QFN20") (libsource (lib "UDAC") (part "TPS7A4701")))
    (comp (ref "UP2") (value "TPS7A3301") (footprint "QFN20") (libsource (lib "UDAC") (part "TPS7A3301")))
    (comp (ref "US1") (value "LTC3544") (footprint "QFN16") (libsource (lib "UDAC") (part "LTC3544")))
    (comp (ref "US2") (value "MIC94310") (footprint "DFN4") (libsource (lib "UDAC") (part "MIC94310")))
    (comp (ref "US3") (value "TPS71725") (footprint "SC705") (libsource (lib "UDAC") (part "TPS71725")))
    (comp (ref "US4") (value "TPS61170") (footprint "DFN6") (libsource (lib "UDAC") (part "TPS61170")))
    (comp (ref "XC1")
      (value "XTAL")
      (footprint "2520")
      (description "Crystal Oscillator")
      (fields (field (name "PUBLISHER") "Altium Limited"))
      (libsource (lib "Miscellaneous Devices") (part "XTAL"))
    )
    (comp (ref "XD1")
      (value "XTAL")
      (footprint "2016")
      (description "Crystal Oscillator")
      (fields (field (name "PUBLISHER") "Altium Limited"))
      (libsource (lib "Miscellaneous Devices") (part "XTAL"))
    )
    (comp (ref "XD2")
      (value "XTAL")
      (footprint "2016")
      (description "Crystal Oscillator")
      (fields (field (name "PUBLISHER") "Altium Limited"))
      (libsource (lib "Miscellaneous Devices") (part "XTAL"))
    )
  )
  (nets
    (net (code "1") (name "/1V1") (class "Default")
      (node (ref "BD1") (pin "2") (pinfunction "2_2") (pintype "passive"))
      (node (ref "CDD") (pin "1") (pinfunction "1_1") (pintype "passive"))
      (node (ref "CDE") (pin "1") (pinfunction "1_1") (pintype "passive"))
      (node (ref "CDF") (pin "1") (pinfunction "1_1") (pintype "passive"))
      (node (ref "CDG") (pin "1") (pinfunction "1_1") (pintype "passive"))
      (node (ref "CS4") (pin "2") (pinfunction "2_2") (pintype "passive"))
      (node (ref "CS5") (pin "1") (pinfunction "1_1") (pintype "passive"))
      (node (ref "LS1") (pin "2") (pinfunction "2_2") (pintype "passive"))
      (node (ref "RS1") (pin "1") (pinfunction "1_1") (pintype "passive"))
      (node (ref "UD2") (pin "F8") (pinfunction "VDD_F8") (pintype "power_in"))
      (node (ref "UD2") (pin "G6") (pinfunction "VDD_G6") (pintype "power_in"))
      (node (ref "UD2") (pin "H9") (pinfunction "VDD_H9") (pintype "power_in"))
      (node (ref "UD2") (pin "J4") (pinfunction "VDD_J4") (pintype "power_in"))
      (node (ref "UD2") (pin "J7") (pinfunction "VDD_J7") (pintype "power_in"))
    )
    (net (code "2") (name "/1V2") (class "Default")
      (node (ref "CD7") (pin "2") (pinfunction "2_2") (pintype "passive"))
      (node (ref "CD8") (pin "2") (pinfunction "2_2") (pintype "passive"))
      (node (ref "CD9") (pin "2") (pinfunction "2_2") (pintype "passive"))
      (node (ref "CDA") (pin "2") (pinfunction "2_2") (pintype "passive"))
      (node (ref "CDB") (pin "2") (pinfunction "2_2") (pintype "passive"))
      (node (ref "CDC") (pin "2") (pinfunction "2_2") (pintype "passive"))
      (node (ref "CS6") (pin "1") (pinfunction "1_1") (pintype "passive"))
      (node (ref "CS7") (pin "1") (pinfunction "1_1") (pintype "passive"))
      (node (ref "LS2") (pin "2") (pinfunction "2_2") (pintype "passive"))
      (node (ref "RS3") (pin "1") (pinfunction "1_1") (pintype "passive"))
      (node (ref "UD1") (pin "14") (pinfunction "VIN_14") (pintype "passive"))
      (node (ref "UD1") (pin "30") (pinfunction "VIN_30") (pintype "passive"))
      (node (ref "UD1") (pin "51") (pinfunction "VIN_51") (pintype "passive"))
      (node (ref "UD1") (pin "61") (pinfunction "VIN_61") (pintype "passive"))
      (node (ref "UD1") (pin "81") (pinfunction "VIN_81") (pintype "passive"))
    )
    (net (code "3") (name "/2D5") (class "Default")
      (node (ref "CDJ") (pin "2") (pinfunction "2_2") (pintype "passive"))
      (node (ref "CDK") (pin "2") (pinfunction "2_2") (pintype "passive"))
      (node (ref "UD2") (pin "A14") (pinfunction "VPP_A14") (pintype "power_in"))
    )
    (net (code "4") (name "/2V5") (class "Default")
      (node (ref "CC1") (pin "2") (pinfunction "2_2") (pintype "passive"))
      (node (ref "CC2") (pin "2") (pinfunction "2_2") (pintype "passive"))
      (node (ref "CC3") (pin "2") (pinfunction "2_2") (pintype "passive"))
      (node (ref "CC4") (pin "2") (pinfunction "2_2") (pintype "passive"))
      (node (ref "CC5") (pin "2") (pinfunction "2_2") (pintype "passive"))
      (node (ref "CC6") (pin "2") (pinfunction "2_2") (pintype "passive"))
      (node (ref "CSI") (pin "1") (pinfunction "1_1") (pintype "passive"))
      (node (ref "CSJ") (pin "2") (pinfunction "2_2") (pintype "passive"))
      (node (ref "UC1") (pin "14") (pinfunction "VDD_14") (pintype "passive"))
      (node (ref "UC1") (pin "18") (pinfunction "VDD_18") (pintype "passive"))
      (node (ref "UC1") (pin "2") (pinfunction "VDD_2") (pintype "passive"))
      (node (ref "UC1") (pin "22") (pinfunction "SEL_22") (pintype "passive"))
      (node (ref "UC1") (pin "23") (pinfunction "VDD_23") (pintype "passive"))
      (node (ref "UC1") (pin "24") (pinfunction "OE_24") (pintype "passive"))
      (node (ref "UC1") (pin "6") (pinfunction "VDD_6") (pintype "passive"))
      (node (ref "UC1") (pin "8") (pinfunction "VDD_8") (pintype "passive"))
      (node (ref "US3") (pin "5") (pinfunction "OUT_5") (pintype "passive"))
    )
    (net (code "5") (name "/2V8") (class "Default")
      (node (ref "BS1") (pin "1") (pinfunction "1_1") (pintype "passive"))
      (node (ref "CDN") (pin "2") (pinfunction "2_2") (pintype "passive"))
      (node (ref "CDO") (pin "2") (pinfunction "2_2") (pintype "passive"))
      (node (ref "CDP") (pin "2") (pinfunction "2_2") (pintype "passive"))
      (node (ref "CDQ") (pin "2") (pinfunction "2_2") (pintype "passive"))
      (node (ref "CDR") (pin "2") (pinfunction "2_2") (pintype "passive"))
      (node (ref "CDS") (pin "2") (pinfunction "2_2") (pintype "passive"))
      (node (ref "CSD") (pin "1") (pinfunction "1_1") (pintype "passive"))
      (node (ref "CSE") (pin "2") (pinfunction "2_2") (pintype "passive"))
      (node (ref "UD2") (pin "A8") (pinfunction "VDD_A8") (pintype "passive"))
      (node (ref "UD2") (pin "E3") (pinfunction "VDD_E3") (pintype "passive"))
      (node (ref "UD2") (pin "F6") (pinfunction "VDD_F6") (pintype "passive"))
      (node (ref "UD2") (pin "F9") (pinfunction "VDD_F9") (pintype "passive"))
      (node (ref "UD2") (pin "H14") (pinfunction "VDD_H14") (pintype "passive"))
      (node (ref "UD2") (pin "J6") (pinfunction "VDD_J6") (pintype "passive"))
      (node (ref "UD2") (pin "K1") (pinfunction "VDD_K1") (pintype "passive"))
      (node (ref "US2") (pin "1") (pinfunction "OUT_1") (pintype "passive"))
    )
    (net (code "6") (name "/3V3") (class "Default")
      (node (ref "CD1") (pin "1") (pinfunction "1_1") (pintype "passive"))
      (node (ref "CD2") (pin "1") (pinfunction "1_1") (pintype "passive"))
      (node (ref "CD3") (pin "1") (pinfunction "1_1") (pintype "passive"))
      (node (ref "CD4") (pin "1") (pinfunction "1_1") (pintype "passive"))
      (node (ref "CD5") (pin "1") (pinfunction "1_1") (pintype "passive"))
      (node (ref "CD6") (pin "1") (pinfunction "1_1") (pintype "passive"))
      (node (ref "CDL") (pin "2") (pinfunction "2_2") (pintype "passive"))
      (node (ref "CDM") (pin "2") (pinfunction "2_2") (pintype "passive"))
      (node (ref "CDX") (pin "1") (pinfunction "1_1") (pintype "passive"))
      (node (ref "CSA") (pin "1") (pinfunction "1_1") (pintype "passive"))
      (node (ref "CSB") (pin "1") (pinfunction "1_1") (pintype "passive"))
      (node (ref "LS4") (pin "2") (pinfunction "2_2") (pintype "passive"))
      (node (ref "RD3") (pin "2") (pinfunction "2_2") (pintype "passive"))
      (node (ref "RD4") (pin "2") (pinfunction "2_2") (pintype "passive"))
      (node (ref "RD5") (pin "2") (pinfunction "2_2") (pintype "passive"))
      (node (ref "RD6") (pin "2") (pinfunction "2_2") (pintype "passive"))
      (node (ref "RD9") (pin "2") (pinfunction "2_2") (pintype "passive"))
      (node (ref "RS7") (pin "1") (pinfunction "1_1") (pintype "passive"))
      (node (ref "UD1") (pin "11") (pinfunction "VEX_11") (pintype "passive"))
      (node (ref "UD1") (pin "17") (pinfunction "VEX_17") (pintype "passive"))
      (node (ref "UD1") (pin "22") (pinfunction "VEX_22") (pintype "passive"))
      (node (ref "UD1") (pin "26") (pinfunction "VEX_26") (pintype "passive"))
      (node (ref "UD1") (pin "36") (pinfunction "VEX_36") (pintype "passive"))
      (node (ref "UD1") (pin "4") (pinfunction "VEX_4") (pintype "passive"))
      (node (ref "UD1") (pin "41") (pinfunction "VEX_41") (pintype "passive"))
      (node (ref "UD1") (pin "49") (pinfunction "VEX_49") (pintype "passive"))
      (node (ref "UD1") (pin "50") (pinfunction "VEX_50") (pintype "passive"))
      (node (ref "UD1") (pin "55") (pinfunction "VEX_55") (pintype "passive"))
      (node (ref "UD1") (pin "62") (pinfunction "VEX_62") (pintype "passive"))
      (node (ref "UD1") (pin "66") (pinfunction "BM0_66") (pintype "passive"))
      (node (ref "UD1") (pin "72") (pinfunction "VEX_72") (pintype "passive"))
      (node (ref "UD1") (pin "77") (pinfunction "~{NMI}_77") (pintype "passive"))
      (node (ref "UD1") (pin "79") (pinfunction "WAK_79") (pintype "passive"))
      (node (ref "UD1") (pin "82") (pinfunction "VEX_82") (pintype "passive"))
      (node (ref "UD2") (pin "J9") (pinfunction "VDD_J9") (pintype "passive"))
      (node (ref "UD2") (pin "L11") (pinfunction "VDD_L11") (pintype "passive"))
      (node (ref "UD2") (pin "M5") (pinfunction "VDD_M5") (pintype "passive"))
      (node (ref "UD3") (pin "1") (pinfunction "VDD_1") (pintype "passive"))
      (node (ref "UD4") (pin "3") (pinfunction "~{WP}_3") (pintype "passive"))
      (node (ref "UD4") (pin "7") (pinfunction "~{HLD}_7") (pintype "passive"))
      (node (ref "UD4") (pin "8") (pinfunction "VDD_8") (pintype "passive"))
    )
    (net (code "7") (name "/5V0") (class "Default")
      (node (ref "CS1") (pin "1") (pinfunction "1_1") (pintype "passive"))
      (node (ref "CS2") (pin "1") (pinfunction "1_1") (pintype "passive"))
      (node (ref "CSK") (pin "2") (pinfunction "2_2") (pintype "passive"))
      (node (ref "CSL") (pin "1") (pinfunction "1_1") (pintype "passive"))
      (node (ref "FD1") (pin "1") (pinfunction "1_1") (pintype "passive"))
      (node (ref "RD7") (pin "1") (pinfunction "1_1") (pintype "passive"))
    )
    (net (code "8") (name "/8N0") (class "Default")
      (node (ref "CPS") (pin "2") (pinfunction "2_2") (pintype "passive"))
      (node (ref "CPT") (pin "2") (pinfunction "2_2") (pintype "passive"))
      (node (ref "RP7") (pin "1") (pinfunction "1_1") (pintype "passive"))
      (node (ref "RP8") (pin "1") (pinfunction "1_1") (pintype "passive"))
    )
    (net (code "9") (name "/8P0") (class "Default")
      (node (ref "CPE") (pin "1") (pinfunction "1_1") (pintype "passive"))
      (node (ref "CPF") (pin "2") (pinfunction "2_2") (pintype "passive"))
      (node (ref "RP4") (pin "1") (pinfunction "1_1") (pintype "passive"))
      (node (ref "RP5") (pin "1") (pinfunction "1_1") (pintype "passive"))
    )
    (net (code "10") (name "/CEN") (class "Default")
      (node (ref "RSA") (pin "1") (pinfunction "1_1") (pintype "passive"))
      (node (ref "UD1") (pin "69") (pinfunction "PA08_69") (pintype "passive"))
    )
    (net (code "11") (name "/CK0") (class "Default")
      (node (ref "RC2") (pin "1") (pinfunction "1_1") (pintype "passive"))
    )
    (net (code "12") (name "/CK1") (class "Default")
      (node (ref "RC1") (pin "1") (pinfunction "1_1") (pintype "passive"))
    )
    (net (code "13") (name "/CK2") (class "Default")
      (node (ref "RC3") (pin "2") (pinfunction "2_2") (pintype "passive"))
    )
    (net (code "14") (name "/CK3") (class "Default")
      (node (ref "RC4") (pin "2") (pinfunction "2_2") (pintype "passive"))
    )
    (net (code "15") (name "/CK4") (class "Default")
      (node (ref "RC5") (pin "2") (pinfunction "2_2") (pintype "passive"))
      (node (ref "UD2") (pin "M12") (pinfunction "R109_M12") (pintype "passive"))
    )
    (net (code "16") (name "/FB") (class "Default")
      (node (ref "CPA") (pin "1") (pinfunction "1_1") (pintype "passive"))
      (node (ref "RP1") (pin "2") (pinfunction "2_2") (pintype "passive"))
      (node (ref "RP2") (pin "1") (pinfunction "1_1") (pintype "passive"))
      (node (ref "US4") (pin "1") (pinfunction "FB_1") (pintype "passive"))
    )
    (net (code "17") (name "/FCD") (class "Default")
      (node (ref "RD4") (pin "1") (pinfunction "1_1") (pintype "passive"))
      (node (ref "UD1") (pin "75") (pinfunction "PA03_75") (pintype "passive"))
      (node (ref "UD2") (pin "M10") (pinfunction "DNE_M10") (pintype "passive"))
    )
    (net (code "18") (name "/FCI") (class "Default")
      (node (ref "UD1") (pin "78") (pinfunction "PA02_78") (pintype "passive"))
      (node (ref "UD2") (pin "P11") (pinfunction "SDI_P11") (pintype "passive"))
    )
    (net (code "19") (name "/FCK") (class "Default")
      (node (ref "RDC") (pin "2") (pinfunction "2_2") (pintype "passive"))
      (node (ref "UD1") (pin "88") (pinfunction "PA00_88") (pintype "passive"))
      (node (ref "UD2") (pin "P12") (pinfunction "SCK_P12") (pintype "passive"))
    )
    (net (code "20") (name "/FCO") (class "Default")
      (node (ref "UD1") (pin "80") (pinfunction "PA01_80") (pintype "passive"))
      (node (ref "UD2") (pin "M11") (pinfunction "SDO_M11") (pintype "passive"))
    )
    (net (code "21") (name "/FCR") (class "Default")
      (node (ref "RD5") (pin "1") (pinfunction "1_1") (pintype "passive"))
      (node (ref "UD1") (pin "73") (pinfunction "PA05_73") (pintype "passive"))
      (node (ref "UD2") (pin "L10") (pinfunction "~{RST}_L10") (pintype "passive"))
    )
    (net (code "22") (name "/FCS") (class "Default")
      (node (ref "RDB") (pin "2") (pinfunction "2_2") (pintype "passive"))
      (node (ref "UD1") (pin "74") (pinfunction "PA04_74") (pintype "passive"))
      (node (ref "UD2") (pin "P13") (pinfunction "~{CS}_P13") (pintype "passive"))
    )
    (net (code "23") (name "/FD0") (class "Default")
      (node (ref "UD1") (pin "42") (pinfunction "PB07_42") (pintype "passive"))
      (node (ref "UD2") (pin "M9") (pinfunction "B91_M9") (pintype "passive"))
    )
    (net (code "24") (name "/FD1") (class "Default")
      (node (ref "UD1") (pin "43") (pinfunction "PB06_43") (pintype "passive"))
      (node (ref "UD2") (pin "P9") (pinfunction "B89_P9") (pintype "passive"))
    )
    (net (code "25") (name "/FD2") (class "Default")
      (node (ref "UD1") (pin "44") (pinfunction "PB05_44") (pintype "passive"))
      (node (ref "UD2") (pin "P8") (pinfunction "B82_P8") (pintype "passive"))
    )
    (net (code "26") (name "/FD3") (class "Default")
      (node (ref "UD1") (pin "45") (pinfunction "PB04_45") (pintype "passive"))
      (node (ref "UD2") (pin "P7") (pinfunction "B81_P7") (pintype "passive"))
    )
    (net (code "27") (name "/FD4") (class "Default")
      (node (ref "UD1") (pin "46") (pinfunction "PB03_46") (pintype "passive"))
      (node (ref "UD2") (pin "P5") (pinfunction "B74_P5") (pintype "passive"))
    )
    (net (code "28") (name "/FD5") (class "Default")
      (node (ref "UD1") (pin "47") (pinfunction "PB02_47") (pintype "passive"))
      (node (ref "UD2") (pin "P4") (pinfunction "B73_P4") (pintype "passive"))
    )
    (net (code "29") (name "/FD6") (class "Default")
      (node (ref "UD1") (pin "48") (pinfunction "PB01_48") (pintype "passive"))
      (node (ref "UD2") (pin "P3") (pinfunction "B59_P3") (pintype "passive"))
    )
    (net (code "30") (name "/FD7") (class "Default")
      (node (ref "UD1") (pin "52") (pinfunction "PB00_52") (pintype "passive"))
      (node (ref "UD2") (pin "P2") (pinfunction "B56_P2") (pintype "passive"))
    )
    (net (code "31") (name "/FDK") (class "Default")
      (node (ref "UD1") (pin "54") (pinfunction "PA14_54") (pintype "passive"))
      (node (ref "UD2") (pin "M3") (pinfunction "B64_M3") (pintype "passive"))
    )
    (net (code "32") (name "/GND") (class "Default")
      (node (ref "BD2") (pin "2") (pinfunction "2_2") (pintype "passive"))
      (node (ref "CC1") (pin "1") (pinfunction "1_1") (pintype "passive"))
      (node (ref "CC2") (pin "1") (pinfunction "1_1") (pintype "passive"))
      (node (ref "CC3") (pin "1") (pinfunction "1_1") (pintype "passive"))
      (node (ref "CC4") (pin "1") (pinfunction "1_1") (pintype "passive"))
      (node (ref "CC5") (pin "1") (pinfunction "1_1") (pintype "passive"))
      (node (ref "CC6") (pin "1") (pinfunction "1_1") (pintype "passive"))
      (node (ref "CC7") (pin "1") (pinfunction "1_1") (pintype "passive"))
      (node (ref "CC8") (pin "1") (pinfunction "1_1") (pintype "passive"))
      (node (ref "CC9") (pin "2") (pinfunction "2_2") (pintype "passive"))
      (node (ref "CCA") (pin "2") (pinfunction "2_2") (pintype "passive"))
      (node (ref "CCB") (pin "2") (pinfunction "2_2") (pintype "passive"))
      (node (ref "CCC") (pin "2") (pinfunction "2_2") (pintype "passive"))
      (node (ref "CD1") (pin "2") (pinfunction "2_2") (pintype "passive"))
      (node (ref "CD2") (pin "2") (pinfunction "2_2") (pintype "passive"))
      (node (ref "CD3") (pin "2") (pinfunction "2_2") (pintype "passive"))
      (node (ref "CD4") (pin "2") (pinfunction "2_2") (pintype "passive"))
      (node (ref "CD5") (pin "2") (pinfunction "2_2") (pintype "passive"))
      (node (ref "CD6") (pin "2") (pinfunction "2_2") (pintype "passive"))
      (node (ref "CD7") (pin "1") (pinfunction "1_1") (pintype "passive"))
      (node (ref "CD8") (pin "1") (pinfunction "1_1") (pintype "passive"))
      (node (ref "CD9") (pin "1") (pinfunction "1_1") (pintype "passive"))
      (node (ref "CDA") (pin "1") (pinfunction "1_1") (pintype "passive"))
      (node (ref "CDB") (pin "1") (pinfunction "1_1") (pintype "passive"))
      (node (ref "CDC") (pin "1") (pinfunction "1_1") (pintype "passive"))
      (node (ref "CDD") (pin "2") (pinfunction "2_2") (pintype "passive"))
      (node (ref "CDE") (pin "2") (pinfunction "2_2") (pintype "passive"))
      (node (ref "CDF") (pin "2") (pinfunction "2_2") (pintype "passive"))
      (node (ref "CDG") (pin "2") (pinfunction "2_2") (pintype "passive"))
      (node (ref "CDJ") (pin "1") (pinfunction "1_1") (pintype "passive"))
      (node (ref "CDK") (pin "1") (pinfunction "1_1") (pintype "passive"))
      (node (ref "CDL") (pin "1") (pinfunction "1_1") (pintype "passive"))
      (node (ref "CDM") (pin "1") (pinfunction "1_1") (pintype "passive"))
      (node (ref "CDN") (pin "1") (pinfunction "1_1") (pintype "passive"))
      (node (ref "CDO") (pin "1") (pinfunction "1_1") (pintype "passive"))
      (node (ref "CDP") (pin "1") (pinfunction "1_1") (pintype "passive"))
      (node (ref "CDQ") (pin "1") (pinfunction "1_1") (pintype "passive"))
      (node (ref "CDR") (pin "1") (pinfunction "1_1") (pintype "passive"))
      (node (ref "CDS") (pin "1") (pinfunction "1_1") (pintype "passive"))
      (node (ref "CDT") (pin "1") (pinfunction "1_1") (pintype "passive"))
      (node (ref "CDU") (pin "1") (pinfunction "1_1") (pintype "passive"))
      (node (ref "CDV") (pin "1") (pinfunction "1_1") (pintype "passive"))
      (node (ref "CDW") (pin "1") (pinfunction "1_1") (pintype "passive"))
      (node (ref "CDX") (pin "2") (pinfunction "2_2") (pintype "passive"))
      (node (ref "CP2") (pin "1") (pinfunction "1_1") (pintype "passive"))
      (node (ref "CP3") (pin "1") (pinfunction "1_1") (pintype "passive"))
      (node (ref "CP4") (pin "1") (pinfunction "1_1") (pintype "passive"))
      (node (ref "CP5") (pin "1") (pinfunction "1_1") (pintype "passive"))
      (node (ref "CP6") (pin "2") (pinfunction "2_2") (pintype "passive"))
      (node (ref "CP7") (pin "1") (pinfunction "1_1") (pintype "passive"))
      (node (ref "CP8") (pin "2") (pinfunction "2_2") (pintype "passive"))
      (node (ref "CP9") (pin "1") (pinfunction "1_1") (pintype "passive"))
      (node (ref "CPB") (pin "2") (pinfunction "2_2") (pintype "passive"))
      (node (ref "CPC") (pin "1") (pinfunction "1_1") (pintype "passive"))
      (node (ref "CPE") (pin "2") (pinfunction "2_2") (pintype "passive"))
      (node (ref "CPF") (pin "1") (pinfunction "1_1") (pintype "passive"))
      (node (ref "CPH") (pin "1") (pinfunction "1_1") (pintype "passive"))
      (node (ref "CPI") (pin "1") (pinfunction "1_1") (pintype "passive"))
      (node (ref "CPJ") (pin "1") (pinfunction "1_1") (pintype "passive"))
      (node (ref "CPK") (pin "1") (pinfunction "1_1") (pintype "passive"))
      (node (ref "CPL") (pin "1") (pinfunction "1_1") (pintype "passive"))
      (node (ref "CPM") (pin "1") (pinfunction "1_1") (pintype "passive"))
      (node (ref "CPN") (pin "1") (pinfunction "1_1") (pintype "passive"))
      (node (ref "CPO") (pin "1") (pinfunction "1_1") (pintype "passive"))
      (node (ref "CPP") (pin "1") (pinfunction "1_1") (pintype "passive"))
      (node (ref "CPQ") (pin "1") (pinfunction "1_1") (pintype "passive"))
      (node (ref "CPS") (pin "1") (pinfunction "1_1") (pintype "passive"))
      (node (ref "CPT") (pin "1") (pinfunction "1_1") (pintype "passive"))
      (node (ref "CS1") (pin "2") (pinfunction "2_2") (pintype "passive"))
      (node (ref "CS2") (pin "3") (pinfunction "3_3") (pintype "passive"))
      (node (ref "CS3") (pin "2") (pinfunction "2_2") (pintype "passive"))
      (node (ref "CS5") (pin "2") (pinfunction "2_2") (pintype "passive"))
      (node (ref "CS7") (pin "2") (pinfunction "2_2") (pintype "passive"))
      (node (ref "CS9") (pin "2") (pinfunction "2_2") (pintype "passive"))
      (node (ref "CSB") (pin "2") (pinfunction "2_2") (pintype "passive"))
      (node (ref "CSC") (pin "1") (pinfunction "1_1") (pintype "passive"))
      (node (ref "CSD") (pin "2") (pinfunction "2_2") (pintype "passive"))
      (node (ref "CSE") (pin "1") (pinfunction "1_1") (pintype "passive"))
      (node (ref "CSF") (pin "2") (pinfunction "2_2") (pintype "passive"))
      (node (ref "CSG") (pin "1") (pinfunction "1_1") (pintype "passive"))
      (node (ref "CSH") (pin "1") (pinfunction "1_1") (pintype "passive"))
      (node (ref "CSI") (pin "2") (pinfunction "2_2") (pintype "passive"))
      (node (ref "CSJ") (pin "1") (pinfunction "1_1") (pintype "passive"))
      (node (ref "CSK") (pin "1") (pinfunction "1_1") (pintype "passive"))
      (node (ref "CSL") (pin "3") (pinfunction "3_3") (pintype "passive"))
      (node (ref "CSM") (pin "1") (pinfunction "1_1") (pintype "passive"))
      (node (ref "DC1") (pin "3") (pinfunction "A_3") (pintype "passive"))
      (node (ref "DC2") (pin "3") (pinfunction "A_3") (pintype "passive"))
      (node (ref "DP1") (pin "1") (pinfunction "A_1") (pintype "passive"))
      (node (ref "DP3") (pin "2") (pinfunction "K_2") (pintype "passive"))
      (node (ref "PD1") (pin "4") (pinfunction "4_4") (pintype "passive"))
      (node (ref "PD2") (pin "8") (pinfunction "8_8") (pintype "passive"))
      (node (ref "RDA") (pin "1") (pinfunction "1_1") (pintype "passive"))
      (node (ref "RDB") (pin "1") (pinfunction "1_1") (pintype "passive"))
      (node (ref "RDC") (pin "1") (pinfunction "1_1") (pintype "passive"))
      (node (ref "RDD") (pin "1") (pinfunction "1_1") (pintype "passive"))
      (node (ref "RP1") (pin "1") (pinfunction "1_1") (pintype "passive"))
      (node (ref "RP3") (pin "2") (pinfunction "2_2") (pintype "passive"))
      (node (ref "RP6") (pin "1") (pinfunction "1_1") (pintype "passive"))
      (node (ref "RS2") (pin "1") (pinfunction "1_1") (pintype "passive"))
      (node (ref "RS4") (pin "1") (pinfunction "1_1") (pintype "passive"))
      (node (ref "RS6") (pin "1") (pinfunction "1_1") (pintype "passive"))
      (node (ref "RS8") (pin "1") (pinfunction "1_1") (pintype "passive"))
      (node (ref "RS9") (pin "1") (pinfunction "1_1") (pintype "passive"))
      (node (ref "RSB") (pin "1") (pinfunction "1_1") (pintype "passive"))
      (node (ref "RSC") (pin "1") (pinfunction "1_1") (pintype "passive"))
      (node (ref "UC1") (pin "1") (pinfunction "GND_1") (pintype "passive"))
      (node (ref "UC1") (pin "11") (pinfunction "GND_11") (pintype "passive"))
      (node (ref "UC1") (pin "12") (pinfunction "GND_12") (pintype "passive"))
      (node (ref "UC1") (pin "16") (pinfunction "GND_16") (pintype "passive"))
      (node (ref "UC1") (pin "19") (pinfunction "GND_19") (pintype "passive"))
      (node (ref "UC1") (pin "25") (pinfunction "GND_25") (pintype "passive"))
      (node (ref "UC1") (pin "4") (pinfunction "GND_4") (pintype "passive"))
      (node (ref "UC1") (pin "7") (pinfunction "GND_7") (pintype "passive"))
      (node (ref "UD1") (pin "21") (pinfunction "RXI_21") (pintype "passive"))
      (node (ref "UD1") (pin "67") (pinfunction "BM1_67") (pintype "passive"))
      (node (ref "UD1") (pin "76") (pinfunction "GND_76") (pintype "passive"))
      (node (ref "UD1") (pin "89") (pinfunction "GND_89") (pintype "passive"))
      (node (ref "UD2") (pin "A9") (pinfunction "GND_A9") (pintype "power_in"))
      (node (ref "UD2") (pin "F1") (pinfunction "GND_F1") (pintype "power_in"))
      (node (ref "UD2") (pin "F7") (pinfunction "GND_F7") (pintype "power_in"))
      (node (ref "UD2") (pin "G7") (pinfunction "GND_G7") (pintype "power_in"))
      (node (ref "UD2") (pin "G8") (pinfunction "GND_G8") (pintype "power_in"))
      (node (ref "UD2") (pin "G9") (pinfunction "GND_G9") (pintype "power_in"))
      (node (ref "UD2") (pin "H6") (pinfunction "GND_H6") (pintype "power_in"))
      (node (ref "UD2") (pin "H7") (pinfunction "GND_H7") (pintype "power_in"))
      (node (ref "UD2") (pin "H8") (pinfunction "GND_H8") (pintype "power_in"))
      (node (ref "UD2") (pin "J14") (pinfunction "GND_J14") (pintype "power_in"))
      (node (ref "UD2") (pin "J8") (pinfunction "GND_J8") (pintype "power_in"))
      (node (ref "UD2") (pin "L3") (pinfunction "GND_L3") (pintype "power_in"))
      (node (ref "UD2") (pin "P6") (pinfunction "GND_P6") (pintype "power_in"))
      (node (ref "UD3") (pin "2") (pinfunction "GND_2") (pintype "passive"))
      (node (ref "UD4") (pin "4") (pinfunction "GND_4") (pintype "passive"))
      (node (ref "UD4") (pin "9") (pinfunction "GND_9") (pintype "passive"))
      (node (ref "UD5") (pin "3") (pinfunction "GND_3") (pintype "passive"))
      (node (ref "UP1") (pin "21") (pinfunction "GND_21") (pintype "passive"))
      (node (ref "UP1") (pin "7") (pinfunction "GND_7") (pintype "passive"))
      (node (ref "UP2") (pin "21") (pinfunction "GND_21") (pintype "passive"))
      (node (ref "UP2") (pin "7") (pinfunction "GND_7") (pintype "passive"))
      (node (ref "US1") (pin "14") (pinfunction "GND_14") (pintype "passive"))
      (node (ref "US1") (pin "17") (pinfunction "GND_17") (pintype "passive"))
      (node (ref "US1") (pin "6") (pinfunction "GND_6") (pintype "passive"))
      (node (ref "US2") (pin "2") (pinfunction "GND_2") (pintype "passive"))
      (node (ref "US2") (pin "5") (pinfunction "GND_5") (pintype "passive"))
      (node (ref "US3") (pin "2") (pinfunction "GND_2") (pintype "passive"))
      (node (ref "US4") (pin "3") (pinfunction "GND_3") (pintype "passive"))
      (node (ref "US4") (pin "7") (pinfunction "GND_7") (pintype "passive"))
    )
    (net (code "33") (name "/L0") (class "Default")
      (node (ref "UD2") (pin "P1") (pinfunction "L25B_P1") (pintype "passive"))
    )
    (net (code "34") (name "/L1") (class "Default")
      (node (ref "UD2") (pin "N1") (pinfunction "L25A_N1") (pintype "passive"))
    )
    (net (code "35") (name "/L2") (class "Default")
      (node (ref "UD2") (pin "M1") (pinfunction "L23B_M1") (pintype "passive"))
    )
    (net (code "36") (name "/L3") (class "Default")
      (node (ref "UD2") (pin "L1") (pinfunction "L23A_L1") (pintype "passive"))
    )
    (net (code "37") (name "/L4") (class "Default")
      (node (ref "UD2") (pin "K3") (pinfunction "L18A_K3") (pintype "passive"))
    )
    (net (code "38") (name "/L5") (class "Default")
      (node (ref "UD2") (pin "J1") (pinfunction "L12B_J1") (pintype "passive"))
    )
    (net (code "39") (name "/L6") (class "Default")
      (node (ref "UD2") (pin "H3") (pinfunction "L14B_H3") (pintype "passive"))
    )
    (net (code "40") (name "/L7") (class "Default")
      (node (ref "UD2") (pin "H1") (pinfunction "L14A_H1") (pintype "passive"))
    )
    (net (code "41") (name "/L8") (class "Default")
      (node (ref "UD2") (pin "G1") (pinfunction "L13B_G1") (pintype "passive"))
    )
    (net (code "42") (name "/L9") (class "Default")
      (node (ref "UD2") (pin "F3") (pinfunction "L9B_F3") (pintype "passive"))
    )
    (net (code "43") (name "/LA") (class "Default")
      (node (ref "UD2") (pin "E1") (pinfunction "L5B_E1") (pintype "passive"))
    )
    (net (code "44") (name "/LB") (class "Default")
      (node (ref "UD2") (pin "D1") (pinfunction "L5A_D1") (pintype "passive"))
    )
    (net (code "45") (name "/LC") (class "Default")
      (node (ref "UD2") (pin "C1") (pinfunction "L2B_C1") (pintype "passive"))
    )
    (net (code "46") (name "/LD") (class "Default")
      (node (ref "UD2") (pin "B1") (pinfunction "L2A_B1") (pintype "passive"))
    )
    (net (code "47") (name "/LE") (class "Default")
      (node (ref "UD2") (pin "A1") (pinfunction "T225_A1") (pintype "passive"))
    )
    (net (code "48") (name "/LF") (class "Default")
      (node (ref "UD2") (pin "A2") (pinfunction "T223_A2") (pintype "passive"))
    )
    (net (code "49") (name "/R0") (class "Default")
      (node (ref "UD2") (pin "A3") (pinfunction "T222_A3") (pintype "passive"))
    )
    (net (code "50") (name "/R1") (class "Default")
      (node (ref "UD2") (pin "A4") (pinfunction "T219_A4") (pintype "passive"))
    )
    (net (code "51") (name "/R2") (class "Default")
      (node (ref "UD2") (pin "A5") (pinfunction "T208_A5") (pintype "passive"))
    )
    (net (code "52") (name "/R3") (class "Default")
      (node (ref "UD2") (pin "A6") (pinfunction "T198_A6") (pintype "passive"))
    )
    (net (code "53") (name "/R4") (class "Default")
      (node (ref "UD2") (pin "A7") (pinfunction "T197_A7") (pintype "passive"))
    )
    (net (code "54") (name "/R5") (class "Default")
      (node (ref "UD2") (pin "A10") (pinfunction "T181_A10") (pintype "passive"))
    )
    (net (code "55") (name "/R6") (class "Default")
      (node (ref "UD2") (pin "A11") (pinfunction "T179_A11") (pintype "passive"))
    )
    (net (code "56") (name "/R7") (class "Default")
      (node (ref "UD2") (pin "A12") (pinfunction "T170_A12") (pintype "passive"))
    )
    (net (code "57") (name "/R8") (class "Default")
      (node (ref "UD2") (pin "B14") (pinfunction "R161_B14") (pintype "passive"))
    )
    (net (code "58") (name "/R9") (class "Default")
      (node (ref "UD2") (pin "C14") (pinfunction "R154_C14") (pintype "passive"))
    )
    (net (code "59") (name "/RA") (class "Default")
      (node (ref "UD2") (pin "D14") (pinfunction "R152_D14") (pintype "passive"))
    )
    (net (code "60") (name "/RB") (class "Default")
      (node (ref "UD2") (pin "E14") (pinfunction "R148_E14") (pintype "passive"))
    )
    (net (code "61") (name "/RC") (class "Default")
      (node (ref "UD2") (pin "F14") (pinfunction "R140_F14") (pintype "passive"))
    )
    (net (code "62") (name "/RD") (class "Default")
      (node (ref "UD2") (pin "G14") (pinfunction "R141_G14") (pintype "passive"))
    )
    (net (code "63") (name "/RE") (class "Default")
      (node (ref "UD2") (pin "K14") (pinfunction "R117_K14") (pintype "passive"))
    )
    (net (code "64") (name "/RF") (class "Default")
      (node (ref "UD2") (pin "L14") (pinfunction "R114_L14") (pintype "passive"))
    )
    (net (code "65") (name "/RMP") (class "Default")
      (node (ref "RSB") (pin "2") (pinfunction "2_2") (pintype "passive"))
      (node (ref "UD1") (pin "64") (pinfunction "PA09_64") (pintype "passive"))
      (node (ref "US4") (pin "5") (pinfunction "CTL_5") (pintype "passive"))
    )
    (net (code "66") (name "/RSI") (class "Default")
      (node (ref "UD1") (pin "27") (pinfunction "PB12_27") (pintype "passive"))
      (node (ref "UD4") (pin "5") (pinfunction "SI_5") (pintype "passive"))
    )
    (net (code "67") (name "/RSK") (class "Default")
      (node (ref "RDD") (pin "2") (pinfunction "2_2") (pintype "passive"))
      (node (ref "UD1") (pin "29") (pinfunction "PB10_29") (pintype "passive"))
      (node (ref "UD4") (pin "6") (pinfunction "SCK_6") (pintype "passive"))
    )
    (net (code "68") (name "/RSO") (class "Default")
      (node (ref "UD1") (pin "28") (pinfunction "PB11_28") (pintype "passive"))
      (node (ref "UD4") (pin "2") (pinfunction "SO_2") (pintype "passive"))
    )
    (net (code "69") (name "/RSS") (class "Default")
      (node (ref "RD6") (pin "1") (pinfunction "1_1") (pintype "passive"))
      (node (ref "UD1") (pin "23") (pinfunction "PB15_23") (pintype "passive"))
      (node (ref "UD4") (pin "1") (pinfunction "~{CS}_1") (pintype "passive"))
    )
    (net (code "70") (name "/RST") (class "Default")
      (node (ref "PD2") (pin "6") (pinfunction "6_6") (pintype "passive"))
      (node (ref "RD3") (pin "1") (pinfunction "1_1") (pintype "passive"))
      (node (ref "UD1") (pin "68") (pinfunction "~{RST}_68") (pintype "passive"))
      (node (ref "UD3") (pin "3") (pinfunction "~{RST}_3") (pintype "passive"))
    )
    (net (code "71") (name "/SW") (class "Default")
      (node (ref "CP1") (pin "1") (pinfunction "1_1") (pintype "passive"))
      (node (ref "CPG") (pin "1") (pinfunction "1_1") (pintype "passive"))
      (node (ref "LS5") (pin "2") (pinfunction "2_2") (pintype "passive"))
      (node (ref "US4") (pin "4") (pinfunction "SW_4") (pintype "passive"))
    )
    (net (code "72") (name "/TCK") (class "Default")
      (node (ref "PD2") (pin "3") (pinfunction "3_3") (pintype "passive"))
      (node (ref "UD1") (pin "85") (pinfunction "TCK_85") (pintype "passive"))
    )
    (net (code "73") (name "/TDI") (class "Default")
      (node (ref "PD2") (pin "4") (pinfunction "4_4") (pintype "passive"))
      (node (ref "UD1") (pin "86") (pinfunction "TDI_86") (pintype "passive"))
    )
    (net (code "74") (name "/TDO") (class "Default")
      (node (ref "RD8") (pin "2") (pinfunction "2_2") (pintype "passive"))
      (node (ref "UD1") (pin "83") (pinfunction "TDO_83") (pintype "passive"))
    )
    (net (code "75") (name "/TMS") (class "Default")
      (node (ref "PD2") (pin "2") (pinfunction "2_2") (pintype "passive"))
      (node (ref "UD1") (pin "84") (pinfunction "TMS_84") (pintype "passive"))
    )
    (net (code "76") (name "/TRS") (class "Default")
      (node (ref "PD2") (pin "5") (pinfunction "5_5") (pintype "passive"))
      (node (ref "RDA") (pin "2") (pinfunction "2_2") (pintype "passive"))
      (node (ref "UD1") (pin "87") (pinfunction "~{TRS}_87") (pintype "passive"))
    )
    (net (code "77") (name "/VCL") (class "Default")
      (node (ref "UD2") (pin "N14") (pinfunction "R112_N14") (pintype "passive"))
    )
    (net (code "78") (name "/VCR") (class "Default")
      (node (ref "UD2") (pin "P14") (pinfunction "R110_P14") (pintype "passive"))
    )
    (net (code "79") (name "/VXA") (class "Default")
      (node (ref "RC6") (pin "2") (pinfunction "2_2") (pintype "passive"))
      (node (ref "UD2") (pin "L12") (pinfunction "R111_L12") (pintype "passive"))
    )
    (net (code "80") (name "/VXB") (class "Default")
      (node (ref "RC7") (pin "2") (pinfunction "2_2") (pintype "passive"))
      (node (ref "UD2") (pin "J12") (pinfunction "R118_J12") (pintype "passive"))
    )
    (net (code "81") (name "Net-(BD2-Pad1)") (class "Default")
      (node (ref "BD2") (pin "1") (pinfunction "1_1") (pintype "passive"))
      (node (ref "PD1") (pin "5") (pinfunction "5_5") (pintype "passive"))
    )
    (net (code "82") (name "Net-(BP2-Pad2)") (class "Default")
      (node (ref "BP2") (pin "2") (pinfunction "2_2") (pintype "passive"))
      (node (ref "CP4") (pin "2") (pinfunction "2_2") (pintype "passive"))
      (node (ref "CP5") (pin "2") (pinfunction "2_2") (pintype "passive"))
      (node (ref "LP2") (pin "1") (pinfunction "1_1") (pintype "passive"))
    )
    (net (code "83") (name "Net-(BP3-Pad2)") (class "Default")
      (node (ref "BP3") (pin "2") (pinfunction "2_2") (pintype "passive"))
      (node (ref "CPJ") (pin "2") (pinfunction "2_2") (pintype "passive"))
      (node (ref "CPK") (pin "2") (pinfunction "2_2") (pintype "passive"))
      (node (ref "LP4") (pin "1") (pinfunction "1_1") (pintype "passive"))
    )
    (net (code "84") (name "Net-(CC7-Pad2)") (class "Default")
      (node (ref "CC7") (pin "2") (pinfunction "2_2") (pintype "passive"))
      (node (ref "RC6") (pin "1") (pinfunction "1_1") (pintype "passive"))
      (node (ref "RC8") (pin "1") (pinfunction "1_1") (pintype "passive"))
    )
    (net (code "85") (name "Net-(CC8-Pad2)") (class "Default")
      (node (ref "CC8") (pin "2") (pinfunction "2_2") (pintype "passive"))
      (node (ref "RC7") (pin "1") (pinfunction "1_1") (pintype "passive"))
      (node (ref "RC9") (pin "1") (pinfunction "1_1") (pintype "passive"))
    )
    (net (code "86") (name "Net-(CC9-Pad1)") (class "Default")
      (node (ref "CC9") (pin "1") (pinfunction "1_1") (pintype "passive"))
      (node (ref "RC8") (pin "2") (pinfunction "2_2") (pintype "passive"))
      (node (ref "RCA") (pin "1") (pinfunction "1_1") (pintype "passive"))
    )
    (net (code "87") (name "Net-(CCA-Pad1)") (class "Default")
      (node (ref "CCA") (pin "1") (pinfunction "1_1") (pintype "passive"))
      (node (ref "RC9") (pin "2") (pinfunction "2_2") (pintype "passive"))
      (node (ref "RCB") (pin "1") (pinfunction "1_1") (pintype "passive"))
    )
    (net (code "88") (name "Net-(CCB-Pad1)") (class "Default")
      (node (ref "CCB") (pin "1") (pinfunction "1_1") (pintype "passive"))
      (node (ref "RCB") (pin "2") (pinfunction "2_2") (pintype "passive"))
      (node (ref "RCD") (pin "1") (pinfunction "1_1") (pintype "passive"))
    )
    (net (code "89") (name "Net-(CCC-Pad1)") (class "Default")
      (node (ref "CCC") (pin "1") (pinfunction "1_1") (pintype "passive"))
      (node (ref "RCA") (pin "2") (pinfunction "2_2") (pintype "passive"))
      (node (ref "RCC") (pin "1") (pinfunction "1_1") (pintype "passive"))
    )
    (net (code "90") (name "Net-(CP6-Pad1)") (class "Default")
      (node (ref "CP6") (pin "1") (pinfunction "1_1") (pintype "passive"))
      (node (ref "CP7") (pin "2") (pinfunction "2_2") (pintype "passive"))
      (node (ref "LP2") (pin "2") (pinfunction "2_2") (pintype "passive"))
      (node (ref "LP3") (pin "1") (pinfunction "1_1") (pintype "passive"))
    )
    (net (code "91") (name "Net-(CPD-Pad2)") (class "Default")
      (node (ref "CPD") (pin "2") (pinfunction "2_2") (pintype "passive"))
      (node (ref "RP5") (pin "2") (pinfunction "2_2") (pintype "passive"))
      (node (ref "UP1") (pin "1") (pinfunction "OUT_1") (pintype "passive"))
      (node (ref "UP1") (pin "20") (pinfunction "OUT_20") (pintype "passive"))
    )
    (net (code "92") (name "Net-(CPL-Pad2)") (class "Default")
      (node (ref "CPL") (pin "2") (pinfunction "2_2") (pintype "passive"))
      (node (ref "CPM") (pin "2") (pinfunction "2_2") (pintype "passive"))
      (node (ref "LP4") (pin "2") (pinfunction "2_2") (pintype "passive"))
      (node (ref "LP5") (pin "1") (pinfunction "1_1") (pintype "passive"))
    )
    (net (code "93") (name "Net-(CPR-Pad2)") (class "Default")
      (node (ref "CPR") (pin "2") (pinfunction "2_2") (pintype "passive"))
      (node (ref "RP8") (pin "2") (pinfunction "2_2") (pintype "passive"))
      (node (ref "UP2") (pin "1") (pinfunction "OUT_1") (pintype "passive"))
      (node (ref "UP2") (pin "20") (pinfunction "OUT_20") (pintype "passive"))
    )
    (net (code "94") (name "Net-(CSN-Pad1)") (class "Default")
      (node (ref "CSN") (pin "1") (pinfunction "1_1") (pintype "passive"))
      (node (ref "RSC") (pin "2") (pinfunction "2_2") (pintype "passive"))
    )
    (net (code "95") (name "Net-(DC1-K)") (class "Default")
      (node (ref "CCD") (pin "1") (pinfunction "1_1") (pintype "passive"))
      (node (ref "DC1") (pin "1") (pinfunction "K_1") (pintype "passive"))
      (node (ref "RCC") (pin "2") (pinfunction "2_2") (pintype "passive"))
    )
    (net (code "96") (name "Net-(DC2-K)") (class "Default")
      (node (ref "CCE") (pin "1") (pinfunction "1_1") (pintype "passive"))
      (node (ref "DC2") (pin "1") (pinfunction "K_1") (pintype "passive"))
      (node (ref "RCD") (pin "2") (pinfunction "2_2") (pintype "passive"))
    )
    (net (code "97") (name "Net-(DP1-K)") (class "Default")
      (node (ref "CP1") (pin "2") (pinfunction "2_2") (pintype "passive"))
      (node (ref "DP1") (pin "2") (pinfunction "K_2") (pintype "passive"))
      (node (ref "DP2") (pin "1") (pinfunction "A_1") (pintype "passive"))
    )
    (net (code "98") (name "Net-(DP2-K)") (class "Default")
      (node (ref "BP2") (pin "1") (pinfunction "1_1") (pintype "passive"))
      (node (ref "CP2") (pin "2") (pinfunction "2_2") (pintype "passive"))
      (node (ref "CP3") (pin "2") (pinfunction "2_2") (pintype "passive"))
      (node (ref "CPA") (pin "2") (pinfunction "2_2") (pintype "passive"))
      (node (ref "DP2") (pin "2") (pinfunction "K_2") (pintype "passive"))
    )
    (net (code "99") (name "Net-(DP3-A)") (class "Default")
      (node (ref "CPG") (pin "2") (pinfunction "2_2") (pintype "passive"))
      (node (ref "DP3") (pin "1") (pinfunction "A_1") (pintype "passive"))
      (node (ref "DP4") (pin "2") (pinfunction "K_2") (pintype "passive"))
    )
    (net (code "100") (name "Net-(DP4-A)") (class "Default")
      (node (ref "BP3") (pin "1") (pinfunction "1_1") (pintype "passive"))
      (node (ref "CPH") (pin "2") (pinfunction "2_2") (pintype "passive"))
      (node (ref "CPI") (pin "2") (pinfunction "2_2") (pintype "passive"))
      (node (ref "DP4") (pin "1") (pinfunction "A_1") (pintype "passive"))
    )
    (net (code "101") (name "Net-(FD1-Pad2)") (class "Default")
      (node (ref "FD1") (pin "2") (pinfunction "2_2") (pintype "passive"))
      (node (ref "PD1") (pin "1") (pinfunction "1_1") (pintype "passive"))
    )
    (net (code "102") (name "Net-(PD1-Pad2)") (class "Default")
      (node (ref "PD1") (pin "2") (pinfunction "2_2") (pintype "passive"))
      (node (ref "UD5") (pin "1") (pinfunction "D-_1") (pintype "passive"))
    )
    (net (code "103") (name "Net-(PD1-Pad3)") (class "Default")
      (node (ref "PD1") (pin "3") (pinfunction "3_3") (pintype "passive"))
      (node (ref "UD5") (pin "2") (pinfunction "D+_2") (pintype "passive"))
    )
    (net (code "104") (name "Net-(PD2-Pad1)") (class "Default")
      (node (ref "PD2") (pin "1") (pinfunction "1_1") (pintype "passive"))
      (node (ref "RD8") (pin "1") (pinfunction "1_1") (pintype "passive"))
    )
    (net (code "105") (name "Net-(PD2-Pad7)") (class "Default")
      (node (ref "PD2") (pin "7") (pinfunction "7_7") (pintype "passive"))
      (node (ref "RD9") (pin "1") (pinfunction "1_1") (pintype "passive"))
    )
    (net (code "106") (name "Net-(RC1-Pad2)") (class "Default")
      (node (ref "RC1") (pin "2") (pinfunction "2_2") (pintype "passive"))
      (node (ref "UC1") (pin "3") (pinfunction "OUT_3") (pintype "passive"))
    )
    (net (code "107") (name "Net-(RC2-Pad2)") (class "Default")
      (node (ref "RC2") (pin "2") (pinfunction "2_2") (pintype "passive"))
      (node (ref "UC1") (pin "5") (pinfunction "OUT_5") (pintype "passive"))
    )
    (net (code "108") (name "Net-(RC3-Pad1)") (class "Default")
      (node (ref "RC3") (pin "1") (pinfunction "1_1") (pintype "passive"))
      (node (ref "UC1") (pin "17") (pinfunction "OUT_17") (pintype "passive"))
    )
    (net (code "109") (name "Net-(RC4-Pad1)") (class "Default")
      (node (ref "RC4") (pin "1") (pinfunction "1_1") (pintype "passive"))
      (node (ref "UC1") (pin "15") (pinfunction "OUT_15") (pintype "passive"))
    )
    (net (code "110") (name "Net-(RC5-Pad1)") (class "Default")
      (node (ref "RC5") (pin "1") (pinfunction "1_1") (pintype "passive"))
      (node (ref "UC1") (pin "13") (pinfunction "OUT_13") (pintype "passive"))
    )
    (net (code "111") (name "Net-(UC1-XI)") (class "Default")
      (node (ref "CCD") (pin "2") (pinfunction "2_2") (pintype "passive"))
      (node (ref "UC1") (pin "9") (pinfunction "XI_9") (pintype "passive"))
      (node (ref "XC1") (pin "2") (pinfunction "OSC2_2") (pintype "passive"))
    )
    (net (code "112") (name "Net-(UC1-XO)") (class "Default")
      (node (ref "CCE") (pin "2") (pinfunction "2_2") (pintype "passive"))
      (node (ref "UC1") (pin "10") (pinfunction "XO_10") (pintype "passive"))
      (node (ref "XC1") (pin "1") (pinfunction "OSC1_1") (pintype "passive"))
    )
    (net (code "113") (name "Net-(UD1D-DM)") (class "Default")
      (node (ref "UD1") (pin "37") (pinfunction "DM_37") (pintype "passive"))
      (node (ref "UD5") (pin "6") (pinfunction "D-_6") (pintype "passive"))
    )
    (net (code "114") (name "Net-(UD1D-DP)") (class "Default")
      (node (ref "UD1") (pin "35") (pinfunction "DP_35") (pintype "passive"))
      (node (ref "UD5") (pin "5") (pinfunction "D+_5") (pintype "passive"))
    )
    (net (code "115") (name "Net-(UD1D-SXI)") (class "Default")
      (node (ref "CDU") (pin "2") (pinfunction "2_2") (pintype "passive"))
      (node (ref "UD1") (pin "57") (pinfunction "SXI_57") (pintype "passive"))
      (node (ref "XD1") (pin "1") (pinfunction "OSC1_1") (pintype "passive"))
    )
    (net (code "116") (name "Net-(UD1D-SXO)") (class "Default")
      (node (ref "RD1") (pin "2") (pinfunction "2_2") (pintype "passive"))
      (node (ref "UD1") (pin "56") (pinfunction "SXO_56") (pintype "passive"))
    )
    (net (code "117") (name "Net-(UD1D-UXI)") (class "Default")
      (node (ref "CDV") (pin "2") (pinfunction "2_2") (pintype "passive"))
      (node (ref "UD1") (pin "32") (pinfunction "UXI_32") (pintype "passive"))
      (node (ref "XD2") (pin "2") (pinfunction "OSC2_2") (pintype "passive"))
    )
    (net (code "118") (name "Net-(UD1D-UXO)") (class "Default")
      (node (ref "RD2") (pin "2") (pinfunction "2_2") (pintype "passive"))
      (node (ref "UD1") (pin "31") (pinfunction "UXO_31") (pintype "passive"))
    )
    (net (code "119") (name "Net-(UD1D-VBS)") (class "Default")
      (node (ref "RD7") (pin "2") (pinfunction "2_2") (pintype "passive"))
      (node (ref "UD1") (pin "34") (pinfunction "VBS_34") (pintype "passive"))
    )
    (net (code "120") (name "Net-(UD2E-GP0)") (class "Default")
      (node (ref "CDH") (pin "2") (pinfunction "2_2") (pintype "passive"))
      (node (ref "UD2") (pin "L7") (pinfunction "GP0_L7") (pintype "power_in"))
    )
    (net (code "121") (name "Net-(UD2E-GP1)") (class "Default")
      (node (ref "CDI") (pin "2") (pinfunction "2_2") (pintype "passive"))
      (node (ref "UD2") (pin "D8") (pinfunction "GP1_D8") (pintype "power_in"))
    )
    (net (code "122") (name "Net-(UD2E-VP0)") (class "Default")
      (node (ref "BD1") (pin "1") (pinfunction "1_1") (pintype "passive"))
      (node (ref "CDH") (pin "1") (pinfunction "1_1") (pintype "passive"))
      (node (ref "CDI") (pin "1") (pinfunction "1_1") (pintype "passive"))
      (node (ref "UD2") (pin "C8") (pinfunction "VP1_C8") (pintype "power_in"))
      (node (ref "UD2") (pin "M8") (pinfunction "VP0_M8") (pintype "power_in"))
    )
    (net (code "123") (name "Net-(UP1-EN)") (class "Default")
      (node (ref "CP8") (pin "1") (pinfunction "1_1") (pintype "passive"))
      (node (ref "CP9") (pin "2") (pinfunction "2_2") (pintype "passive"))
      (node (ref "LP3") (pin "2") (pinfunction "2_2") (pintype "passive"))
      (node (ref "RP2") (pin "2") (pinfunction "2_2") (pintype "passive"))
      (node (ref "UP1") (pin "13") (pinfunction "EN_13") (pintype "passive"))
      (node (ref "UP1") (pin "15") (pinfunction "VIN_15") (pintype "passive"))
      (node (ref "UP1") (pin "16") (pinfunction "VIN_16") (pintype "passive"))
    )
    (net (code "124") (name "Net-(UP1-NR)") (class "Default")
      (node (ref "CPB") (pin "1") (pinfunction "1_1") (pintype "passive"))
      (node (ref "CPC") (pin "2") (pinfunction "2_2") (pintype "passive"))
      (node (ref "UP1") (pin "14") (pinfunction "NR_14") (pintype "passive"))
    )
    (net (code "125") (name "Net-(UP1-SNS)") (class "Default")
      (node (ref "CPD") (pin "1") (pinfunction "1_1") (pintype "passive"))
      (node (ref "RP3") (pin "1") (pinfunction "1_1") (pintype "passive"))
      (node (ref "RP4") (pin "2") (pinfunction "2_2") (pintype "passive"))
      (node (ref "UP1") (pin "3") (pinfunction "SNS_3") (pintype "passive"))
    )
    (net (code "126") (name "Net-(UP2-EN)") (class "Default")
      (node (ref "CPN") (pin "2") (pinfunction "2_2") (pintype "passive"))
      (node (ref "CPO") (pin "2") (pinfunction "2_2") (pintype "passive"))
      (node (ref "LP5") (pin "2") (pinfunction "2_2") (pintype "passive"))
      (node (ref "UP2") (pin "13") (pinfunction "EN_13") (pintype "passive"))
      (node (ref "UP2") (pin "15") (pinfunction "VIN_15") (pintype "passive"))
      (node (ref "UP2") (pin "16") (pinfunction "VIN_16") (pintype "passive"))
    )
    (net (code "127") (name "Net-(UP2-FB)") (class "Default")
      (node (ref "CPR") (pin "1") (pinfunction "1_1") (pintype "passive"))
      (node (ref "RP6") (pin "2") (pinfunction "2_2") (pintype "passive"))
      (node (ref "RP7") (pin "2") (pinfunction "2_2") (pintype "passive"))
      (node (ref "UP2") (pin "3") (pinfunction "FB_3") (pintype "passive"))
    )
    (net (code "128") (name "Net-(UP2-NR)") (class "Default")
      (node (ref "CPP") (pin "2") (pinfunction "2_2") (pintype "passive"))
      (node (ref "CPQ") (pin "2") (pinfunction "2_2") (pintype "passive"))
      (node (ref "UP2") (pin "14") (pinfunction "NR_14") (pintype "passive"))
    )
    (net (code "129") (name "Net-(US1-EN1)") (class "Default")
      (node (ref "CS2") (pin "2") (pinfunction "2_2") (pintype "passive"))
      (node (ref "CS3") (pin "1") (pinfunction "1_1") (pintype "passive"))
      (node (ref "US1") (pin "12") (pinfunction "EN1_12") (pintype "passive"))
      (node (ref "US1") (pin "15") (pinfunction "VIN_15") (pintype "passive"))
      (node (ref "US1") (pin "16") (pinfunction "EN3_16") (pintype "passive"))
      (node (ref "US1") (pin "3") (pinfunction "EN2_3") (pintype "passive"))
      (node (ref "US1") (pin "7") (pinfunction "VIN_7") (pintype "passive"))
      (node (ref "US1") (pin "9") (pinfunction "EN4_9") (pintype "passive"))
    )
    (net (code "130") (name "Net-(US1-FB1)") (class "Default")
      (node (ref "CSA") (pin "2") (pinfunction "2_2") (pintype "passive"))
      (node (ref "RS7") (pin "2") (pinfunction "2_2") (pintype "passive"))
      (node (ref "RS8") (pin "2") (pinfunction "2_2") (pintype "passive"))
      (node (ref "US1") (pin "11") (pinfunction "FB1_11") (pintype "passive"))
    )
    (net (code "131") (name "Net-(US1-FB2)") (class "Default")
      (node (ref "CS8") (pin "2") (pinfunction "2_2") (pintype "passive"))
      (node (ref "RS5") (pin "2") (pinfunction "2_2") (pintype "passive"))
      (node (ref "RS6") (pin "2") (pinfunction "2_2") (pintype "passive"))
      (node (ref "US1") (pin "2") (pinfunction "FB2_2") (pintype "passive"))
    )
    (net (code "132") (name "Net-(US1-FB3)") (class "Default")
      (node (ref "CS6") (pin "2") (pinfunction "2_2") (pintype "passive"))
      (node (ref "RS3") (pin "2") (pinfunction "2_2") (pintype "passive"))
      (node (ref "RS4") (pin "2") (pinfunction "2_2") (pintype "passive"))
      (node (ref "US1") (pin "1") (pinfunction "FB3_1") (pintype "passive"))
    )
    (net (code "133") (name "Net-(US1-FB4)") (class "Default")
      (node (ref "CS4") (pin "1") (pinfunction "1_1") (pintype "passive"))
      (node (ref "RS1") (pin "2") (pinfunction "2_2") (pintype "passive"))
      (node (ref "RS2") (pin "2") (pinfunction "2_2") (pintype "passive"))
      (node (ref "US1") (pin "10") (pinfunction "FB4_10") (pintype "passive"))
    )
    (net (code "134") (name "Net-(US1-SW1)") (class "Default")
      (node (ref "LS4") (pin "1") (pinfunction "1_1") (pintype "passive"))
      (node (ref "US1") (pin "13") (pinfunction "SW1_13") (pintype "passive"))
    )
    (net (code "135") (name "Net-(US1-SW2)") (class "Default")
      (node (ref "LS3") (pin "1") (pinfunction "1_1") (pintype "passive"))
      (node (ref "US1") (pin "5") (pinfunction "SW2_5") (pintype "passive"))
    )
    (net (code "136") (name "Net-(US1-SW3)") (class "Default")
      (node (ref "LS2") (pin "1") (pinfunction "1_1") (pintype "passive"))
      (node (ref "US1") (pin "4") (pinfunction "SW3_4") (pintype "passive"))
    )
    (net (code "137") (name "Net-(US1-SW4)") (class "Default")
      (node (ref "LS1") (pin "1") (pinfunction "1_1") (pintype "passive"))
      (node (ref "US1") (pin "8") (pinfunction "SW4_8") (pintype "passive"))
    )
    (net (code "138") (name "Net-(US2-EN)") (class "Default")
      (node (ref "CS8") (pin "1") (pinfunction "1_1") (pintype "passive"))
      (node (ref "CS9") (pin "1") (pinfunction "1_1") (pintype "passive"))
      (node (ref "CSC") (pin "2") (pinfunction "2_2") (pintype "passive"))
      (node (ref "LS3") (pin "2") (pinfunction "2_2") (pintype "passive"))
      (node (ref "RS5") (pin "1") (pinfunction "1_1") (pintype "passive"))
      (node (ref "US2") (pin "3") (pinfunction "EN_3") (pintype "passive"))
      (node (ref "US2") (pin "4") (pinfunction "VIN_4") (pintype "passive"))
    )
    (net (code "139") (name "Net-(US3-EN)") (class "Default")
      (node (ref "RS9") (pin "2") (pinfunction "2_2") (pintype "passive"))
      (node (ref "RSA") (pin "2") (pinfunction "2_2") (pintype "passive"))
      (node (ref "US3") (pin "3") (pinfunction "EN_3") (pintype "passive"))
    )
    (net (code "140") (name "Net-(US3-NR)") (class "Default")
      (node (ref "CSH") (pin "2") (pinfunction "2_2") (pintype "passive"))
      (node (ref "US3") (pin "4") (pinfunction "NR_4") (pintype "passive"))
    )
    (net (code "141") (name "Net-(US3-VIN)") (class "Default")
      (node (ref "BS1") (pin "2") (pinfunction "2_2") (pintype "passive"))
      (node (ref "CSF") (pin "1") (pinfunction "1_1") (pintype "passive"))
      (node (ref "CSG") (pin "2") (pinfunction "2_2") (pintype "passive"))
      (node (ref "US3") (pin "1") (pinfunction "VIN_1") (pintype "passive"))
    )
    (net (code "142") (name "Net-(US4-CMP)") (class "Default")
      (node (ref "CSN") (pin "2") (pinfunction "2_2") (pintype "passive"))
      (node (ref "US4") (pin "2") (pinfunction "CMP_2") (pintype "passive"))
    )
    (net (code "143") (name "Net-(US4-VIN)") (class "Default")
      (node (ref "CSL") (pin "2") (pinfunction "2_2") (pintype "passive"))
      (node (ref "CSM") (pin "2") (pinfunction "2_2") (pintype "passive"))
      (node (ref "LS5") (pin "1") (pinfunction "1_1") (pintype "passive"))
      (node (ref "US4") (pin "6") (pinfunction "VIN_6") (pintype "passive"))
    )
    (net (code "144") (name "Net-(XD1-OSC2)") (class "Default")
      (node (ref "CDT") (pin "2") (pinfunction "2_2") (pintype "passive"))
      (node (ref "RD1") (pin "1") (pinfunction "1_1") (pintype "passive"))
      (node (ref "XD1") (pin "2") (pinfunction "OSC2_2") (pintype "passive"))
    )
    (net (code "145") (name "Net-(XD2-OSC1)") (class "Default")
      (node (ref "CDW") (pin "2") (pinfunction "2_2") (pintype "passive"))
      (node (ref "RD2") (pin "1") (pinfunction "1_1") (pintype "passive"))
      (node (ref "XD2") (pin "1") (pinfunction "OSC1_1") (pintype "passive"))
    )
    (net (code "146") (name "unconnected-(UC1-CLK-Pad21)") (class "Default")
      (node (ref "UC1") (pin "21") (pinfunction "CLK_21") (pintype "passive"))
    )
    (net (code "147") (name "unconnected-(UC1-~{CLK}-Pad20)") (class "Default")
      (node (ref "UC1") (pin "20") (pinfunction "~{CLK}_20") (pintype "passive"))
    )
    (net (code "148") (name "unconnected-(UD1A-PA06-Pad71)") (class "Default")
      (node (ref "UD1") (pin "71") (pinfunction "PA06_71") (pintype "passive"))
    )
    (net (code "149") (name "unconnected-(UD1A-PA07-Pad70)") (class "Default")
      (node (ref "UD1") (pin "70") (pinfunction "PA07_70") (pintype "passive"))
    )
    (net (code "150") (name "unconnected-(UD1A-PA10-Pad63)") (class "Default")
      (node (ref "UD1") (pin "63") (pinfunction "PA10_63") (pintype "passive"))
    )
    (net (code "151") (name "unconnected-(UD1A-PA11-Pad60)") (class "Default")
      (node (ref "UD1") (pin "60") (pinfunction "PA11_60") (pintype "passive"))
    )
    (net (code "152") (name "unconnected-(UD1A-PA12-Pad59)") (class "Default")
      (node (ref "UD1") (pin "59") (pinfunction "PA12_59") (pintype "passive"))
    )
    (net (code "153") (name "unconnected-(UD1A-PA13-Pad58)") (class "Default")
      (node (ref "UD1") (pin "58") (pinfunction "PA13_58") (pintype "passive"))
    )
    (net (code "154") (name "unconnected-(UD1A-PA15-Pad53)") (class "Default")
      (node (ref "UD1") (pin "53") (pinfunction "PA15_53") (pintype "passive"))
    )
    (net (code "155") (name "unconnected-(UD1B-PB08-Pad40)") (class "Default")
      (node (ref "UD1") (pin "40") (pinfunction "PB08_40") (pintype "passive"))
    )
    (net (code "156") (name "unconnected-(UD1B-PB09-Pad39)") (class "Default")
      (node (ref "UD1") (pin "39") (pinfunction "PB09_39") (pintype "passive"))
    )
    (net (code "157") (name "unconnected-(UD1B-PB13-Pad25)") (class "Default")
      (node (ref "UD1") (pin "25") (pinfunction "PB13_25") (pintype "passive"))
    )
    (net (code "158") (name "unconnected-(UD1B-PB14-Pad24)") (class "Default")
      (node (ref "UD1") (pin "24") (pinfunction "PB14_24") (pintype "passive"))
    )
    (net (code "159") (name "unconnected-(UD1C-PC00-Pad16)") (class "Default")
      (node (ref "UD1") (pin "16") (pinfunction "PC00_16") (pintype "passive"))
    )
    (net (code "160") (name "unconnected-(UD1C-PC01-Pad13)") (class "Default")
      (node (ref "UD1") (pin "13") (pinfunction "PC01_13") (pintype "passive"))
    )
    (net (code "161") (name "unconnected-(UD1C-PC02-Pad10)") (class "Default")
      (node (ref "UD1") (pin "10") (pinfunction "PC02_10") (pintype "passive"))
    )
    (net (code "162") (name "unconnected-(UD1C-PC03-Pad9)") (class "Default")
      (node (ref "UD1") (pin "9") (pinfunction "PC03_9") (pintype "passive"))
    )
    (net (code "163") (name "unconnected-(UD1C-PC04-Pad8)") (class "Default")
      (node (ref "UD1") (pin "8") (pinfunction "PC04_8") (pintype "passive"))
    )
    (net (code "164") (name "unconnected-(UD1C-PC05-Pad7)") (class "Default")
      (node (ref "UD1") (pin "7") (pinfunction "PC05_7") (pintype "passive"))
    )
    (net (code "165") (name "unconnected-(UD1C-PC06-Pad6)") (class "Default")
      (node (ref "UD1") (pin "6") (pinfunction "PC06_6") (pintype "passive"))
    )
    (net (code "166") (name "unconnected-(UD1C-PC07-Pad5)") (class "Default")
      (node (ref "UD1") (pin "5") (pinfunction "PC07_5") (pintype "passive"))
    )
    (net (code "167") (name "unconnected-(UD1C-PC08-Pad3)") (class "Default")
      (node (ref "UD1") (pin "3") (pinfunction "PC08_3") (pintype "passive"))
    )
    (net (code "168") (name "unconnected-(UD1C-PC09-Pad2)") (class "Default")
      (node (ref "UD1") (pin "2") (pinfunction "PC09_2") (pintype "passive"))
    )
    (net (code "169") (name "unconnected-(UD1C-PC10-Pad1)") (class "Default")
      (node (ref "UD1") (pin "1") (pinfunction "PC10_1") (pintype "passive"))
    )
    (net (code "170") (name "unconnected-(UD1D-CKO-Pad12)") (class "Default")
      (node (ref "UD1") (pin "12") (pinfunction "CKO_12") (pintype "passive"))
    )
    (net (code "171") (name "unconnected-(UD1D-OTG-Pad33)") (class "Default")
      (node (ref "UD1") (pin "33") (pinfunction "OTG_33") (pintype "passive"))
    )
    (net (code "172") (name "unconnected-(UD1D-RXO-Pad20)") (class "Default")
      (node (ref "UD1") (pin "20") (pinfunction "RXO_20") (pintype "passive"))
    )
    (net (code "173") (name "unconnected-(UD1D-SCL-Pad19)") (class "Default")
      (node (ref "UD1") (pin "19") (pinfunction "SCL_19") (pintype "passive"))
    )
    (net (code "174") (name "unconnected-(UD1D-SDA-Pad18)") (class "Default")
      (node (ref "UD1") (pin "18") (pinfunction "SDA_18") (pintype "passive"))
    )
    (net (code "175") (name "unconnected-(UD1D-VBC-Pad38)") (class "Default")
      (node (ref "UD1") (pin "38") (pinfunction "VBC_38") (pintype "passive"))
    )
    (net (code "176") (name "unconnected-(UD1D-~{FLT}-Pad65)") (class "Default")
      (node (ref "UD1") (pin "65") (pinfunction "~{FLT}_65") (pintype "passive"))
    )
    (net (code "177") (name "unconnected-(UD1D-~{RSO}-Pad15)") (class "Default")
      (node (ref "UD1") (pin "15") (pinfunction "~{RSO}_15") (pintype "passive"))
    )
    (net (code "178") (name "unconnected-(UD2A-T172-PadC12)") (class "Default")
      (node (ref "UD2") (pin "C12") (pinfunction "T172_C12") (pintype "passive"))
    )
    (net (code "179") (name "unconnected-(UD2A-T174-PadC11)") (class "Default")
      (node (ref "UD2") (pin "C11") (pinfunction "T174_C11") (pintype "passive"))
    )
    (net (code "180") (name "unconnected-(UD2A-T177-PadD10)") (class "Default")
      (node (ref "UD2") (pin "D10") (pinfunction "T177_D10") (pintype "passive"))
    )
    (net (code "181") (name "unconnected-(UD2A-T178-PadD11)") (class "Default")
      (node (ref "UD2") (pin "D11") (pinfunction "T178_D11") (pintype "passive"))
    )
    (net (code "182") (name "unconnected-(UD2A-T186-PadC10)") (class "Default")
      (node (ref "UD2") (pin "C10") (pinfunction "T186_C10") (pintype "passive"))
    )
    (net (code "183") (name "unconnected-(UD2A-T188-PadD9)") (class "Default")
      (node (ref "UD2") (pin "D9") (pinfunction "T188_D9") (pintype "passive"))
    )
    (net (code "184") (name "unconnected-(UD2A-T190-PadC9)") (class "Default")
      (node (ref "UD2") (pin "C9") (pinfunction "T190_C9") (pintype "passive"))
    )
    (net (code "185") (name "unconnected-(UD2A-T200-PadC7)") (class "Default")
      (node (ref "UD2") (pin "C7") (pinfunction "T200_C7") (pintype "passive"))
    )
    (net (code "186") (name "unconnected-(UD2A-T202-PadD7)") (class "Default")
      (node (ref "UD2") (pin "D7") (pinfunction "T202_D7") (pintype "passive"))
    )
    (net (code "187") (name "unconnected-(UD2A-T206-PadC6)") (class "Default")
      (node (ref "UD2") (pin "C6") (pinfunction "T206_C6") (pintype "passive"))
    )
    (net (code "188") (name "unconnected-(UD2A-T207-PadD6)") (class "Default")
      (node (ref "UD2") (pin "D6") (pinfunction "T207_D6") (pintype "passive"))
    )
    (net (code "189") (name "unconnected-(UD2A-T211-PadD5)") (class "Default")
      (node (ref "UD2") (pin "D5") (pinfunction "T211_D5") (pintype "passive"))
    )
    (net (code "190") (name "unconnected-(UD2A-T212-PadC5)") (class "Default")
      (node (ref "UD2") (pin "C5") (pinfunction "T212_C5") (pintype "passive"))
    )
    (net (code "191") (name "unconnected-(UD2A-T221-PadC4)") (class "Default")
      (node (ref "UD2") (pin "C4") (pinfunction "T221_C4") (pintype "passive"))
    )
    (net (code "192") (name "unconnected-(UD2B-R115-PadK12)") (class "Default")
      (node (ref "UD2") (pin "K12") (pinfunction "R115_K12") (pintype "passive"))
    )
    (net (code "193") (name "unconnected-(UD2B-R116-PadK11)") (class "Default")
      (node (ref "UD2") (pin "K11") (pinfunction "R116_K11") (pintype "passive"))
    )
    (net (code "194") (name "unconnected-(UD2B-R119-PadJ11)") (class "Default")
      (node (ref "UD2") (pin "J11") (pinfunction "R119_J11") (pintype "passive"))
    )
    (net (code "195") (name "unconnected-(UD2B-R120-PadH12)") (class "Default")
      (node (ref "UD2") (pin "H12") (pinfunction "R120_H12") (pintype "passive"))
    )
    (net (code "196") (name "unconnected-(UD2B-R128-PadH11)") (class "Default")
      (node (ref "UD2") (pin "H11") (pinfunction "R128_H11") (pintype "passive"))
    )
    (net (code "197") (name "unconnected-(UD2B-R129-PadG12)") (class "Default")
      (node (ref "UD2") (pin "G12") (pinfunction "R129_G12") (pintype "passive"))
    )
    (net (code "198") (name "unconnected-(UD2B-R136-PadG11)") (class "Default")
      (node (ref "UD2") (pin "G11") (pinfunction "R136_G11") (pintype "passive"))
    )
    (net (code "199") (name "unconnected-(UD2B-R137-PadF12)") (class "Default")
      (node (ref "UD2") (pin "F12") (pinfunction "R137_F12") (pintype "passive"))
    )
    (net (code "200") (name "unconnected-(UD2B-R144-PadF11)") (class "Default")
      (node (ref "UD2") (pin "F11") (pinfunction "R144_F11") (pintype "passive"))
    )
    (net (code "201") (name "unconnected-(UD2B-R146-PadE11)") (class "Default")
      (node (ref "UD2") (pin "E11") (pinfunction "R146_E11") (pintype "passive"))
    )
    (net (code "202") (name "unconnected-(UD2B-R147-PadE12)") (class "Default")
      (node (ref "UD2") (pin "E12") (pinfunction "R147_E12") (pintype "passive"))
    )
    (net (code "203") (name "unconnected-(UD2B-R160-PadD12)") (class "Default")
      (node (ref "UD2") (pin "D12") (pinfunction "R160_D12") (pintype "passive"))
    )
    (net (code "204") (name "unconnected-(UD2C-B63-PadM4)") (class "Default")
      (node (ref "UD2") (pin "M4") (pinfunction "B63_M4") (pintype "passive"))
    )
    (net (code "205") (name "unconnected-(UD2C-B71-PadL5)") (class "Default")
      (node (ref "UD2") (pin "L5") (pinfunction "B71_L5") (pintype "passive"))
    )
    (net (code "206") (name "unconnected-(UD2C-B72-PadL4)") (class "Default")
      (node (ref "UD2") (pin "L4") (pinfunction "B72_L4") (pintype "passive"))
    )
    (net (code "207") (name "unconnected-(UD2C-B77-PadM6)") (class "Default")
      (node (ref "UD2") (pin "M6") (pinfunction "B77_M6") (pintype "passive"))
    )
    (net (code "208") (name "unconnected-(UD2C-B78-PadL6)") (class "Default")
      (node (ref "UD2") (pin "L6") (pinfunction "B78_L6") (pintype "passive"))
    )
    (net (code "209") (name "unconnected-(UD2C-B79-PadM7)") (class "Default")
      (node (ref "UD2") (pin "M7") (pinfunction "B79_M7") (pintype "passive"))
    )
    (net (code "210") (name "unconnected-(UD2C-B87-PadL8)") (class "Default")
      (node (ref "UD2") (pin "L8") (pinfunction "B87_L8") (pintype "passive"))
    )
    (net (code "211") (name "unconnected-(UD2C-CB0-PadL9)") (class "Default")
      (node (ref "UD2") (pin "L9") (pinfunction "CB0_L9") (pintype "passive"))
    )
    (net (code "212") (name "unconnected-(UD2C-CB1-PadP10)") (class "Default")
      (node (ref "UD2") (pin "P10") (pinfunction "CB1_P10") (pintype "passive"))
    )
    (net (code "213") (name "unconnected-(UD2D-L4A-PadC3)") (class "Default")
      (node (ref "UD2") (pin "C3") (pinfunction "L4A_C3") (pintype "passive"))
    )
    (net (code "214") (name "unconnected-(UD2D-L4B-PadD3)") (class "Default")
      (node (ref "UD2") (pin "D3") (pinfunction "L4B_D3") (pintype "passive"))
    )
    (net (code "215") (name "unconnected-(UD2D-L8A-PadD4)") (class "Default")
      (node (ref "UD2") (pin "D4") (pinfunction "L8A_D4") (pintype "passive"))
    )
    (net (code "216") (name "unconnected-(UD2D-L8B-PadE4)") (class "Default")
      (node (ref "UD2") (pin "E4") (pinfunction "L8B_E4") (pintype "passive"))
    )
    (net (code "217") (name "unconnected-(UD2D-L9A-PadF4)") (class "Default")
      (node (ref "UD2") (pin "F4") (pinfunction "L9A_F4") (pintype "passive"))
    )
    (net (code "218") (name "unconnected-(UD2D-L10A-PadH4)") (class "Default")
      (node (ref "UD2") (pin "H4") (pinfunction "L10A_H4") (pintype "passive"))
    )
    (net (code "219") (name "unconnected-(UD2D-L10B-PadG4)") (class "Default")
      (node (ref "UD2") (pin "G4") (pinfunction "L10B_G4") (pintype "passive"))
    )
    (net (code "220") (name "unconnected-(UD2D-L12A-PadJ3)") (class "Default")
      (node (ref "UD2") (pin "J3") (pinfunction "L12A_J3") (pintype "passive"))
    )
    (net (code "221") (name "unconnected-(UD2D-L13A-PadG3)") (class "Default")
      (node (ref "UD2") (pin "G3") (pinfunction "L13A_G3") (pintype "passive"))
    )
    (net (code "222") (name "unconnected-(UD2D-L18B-PadK4)") (class "Default")
      (node (ref "UD2") (pin "K4") (pinfunction "L18B_K4") (pintype "passive"))
    )
    (net (code "223") (name "unconnected-(UD2E-VPF-PadA13)") (class "Default")
      (node (ref "UD2") (pin "A13") (pinfunction "VPF_A13") (pintype "power_in"))
    )
    (net (code "224") (name "unconnected-(UD5-NC-Pad4)") (class "Default")
      (node (ref "UD5") (pin "4") (pinfunction "NC_4") (pintype "passive"))
    )
    (net (code "225") (name "unconnected-(UP1-0V1-Pad12)") (class "Default")
      (node (ref "UP1") (pin "12") (pinfunction "0V1_12") (pintype "passive"))
    )
    (net (code "226") (name "unconnected-(UP1-0V2-Pad11)") (class "Default")
      (node (ref "UP1") (pin "11") (pinfunction "0V2_11") (pintype "passive"))
    )
    (net (code "227") (name "unconnected-(UP1-0V4-Pad10)") (class "Default")
      (node (ref "UP1") (pin "10") (pinfunction "0V4_10") (pintype "passive"))
    )
    (net (code "228") (name "unconnected-(UP1-0V8-Pad9)") (class "Default")
      (node (ref "UP1") (pin "9") (pinfunction "0V8_9") (pintype "passive"))
    )
    (net (code "229") (name "unconnected-(UP1-1V6-Pad8)") (class "Default")
      (node (ref "UP1") (pin "8") (pinfunction "1V6_8") (pintype "passive"))
    )
    (net (code "230") (name "unconnected-(UP1-3V2-Pad6)") (class "Default")
      (node (ref "UP1") (pin "6") (pinfunction "3V2_6") (pintype "passive"))
    )
    (net (code "231") (name "unconnected-(UP1-6V4-Pad4)") (class "Default")
      (node (ref "UP1") (pin "4") (pinfunction "6V4_4") (pintype "passive"))
    )
    (net (code "232") (name "unconnected-(UP1-6V4-Pad5)") (class "Default")
      (node (ref "UP1") (pin "5") (pinfunction "6V4_5") (pintype "passive"))
    )
  )
)
